# draft5_4lyr_autoroute.net
KiCad netlist of a schematic drawn in EAGLE
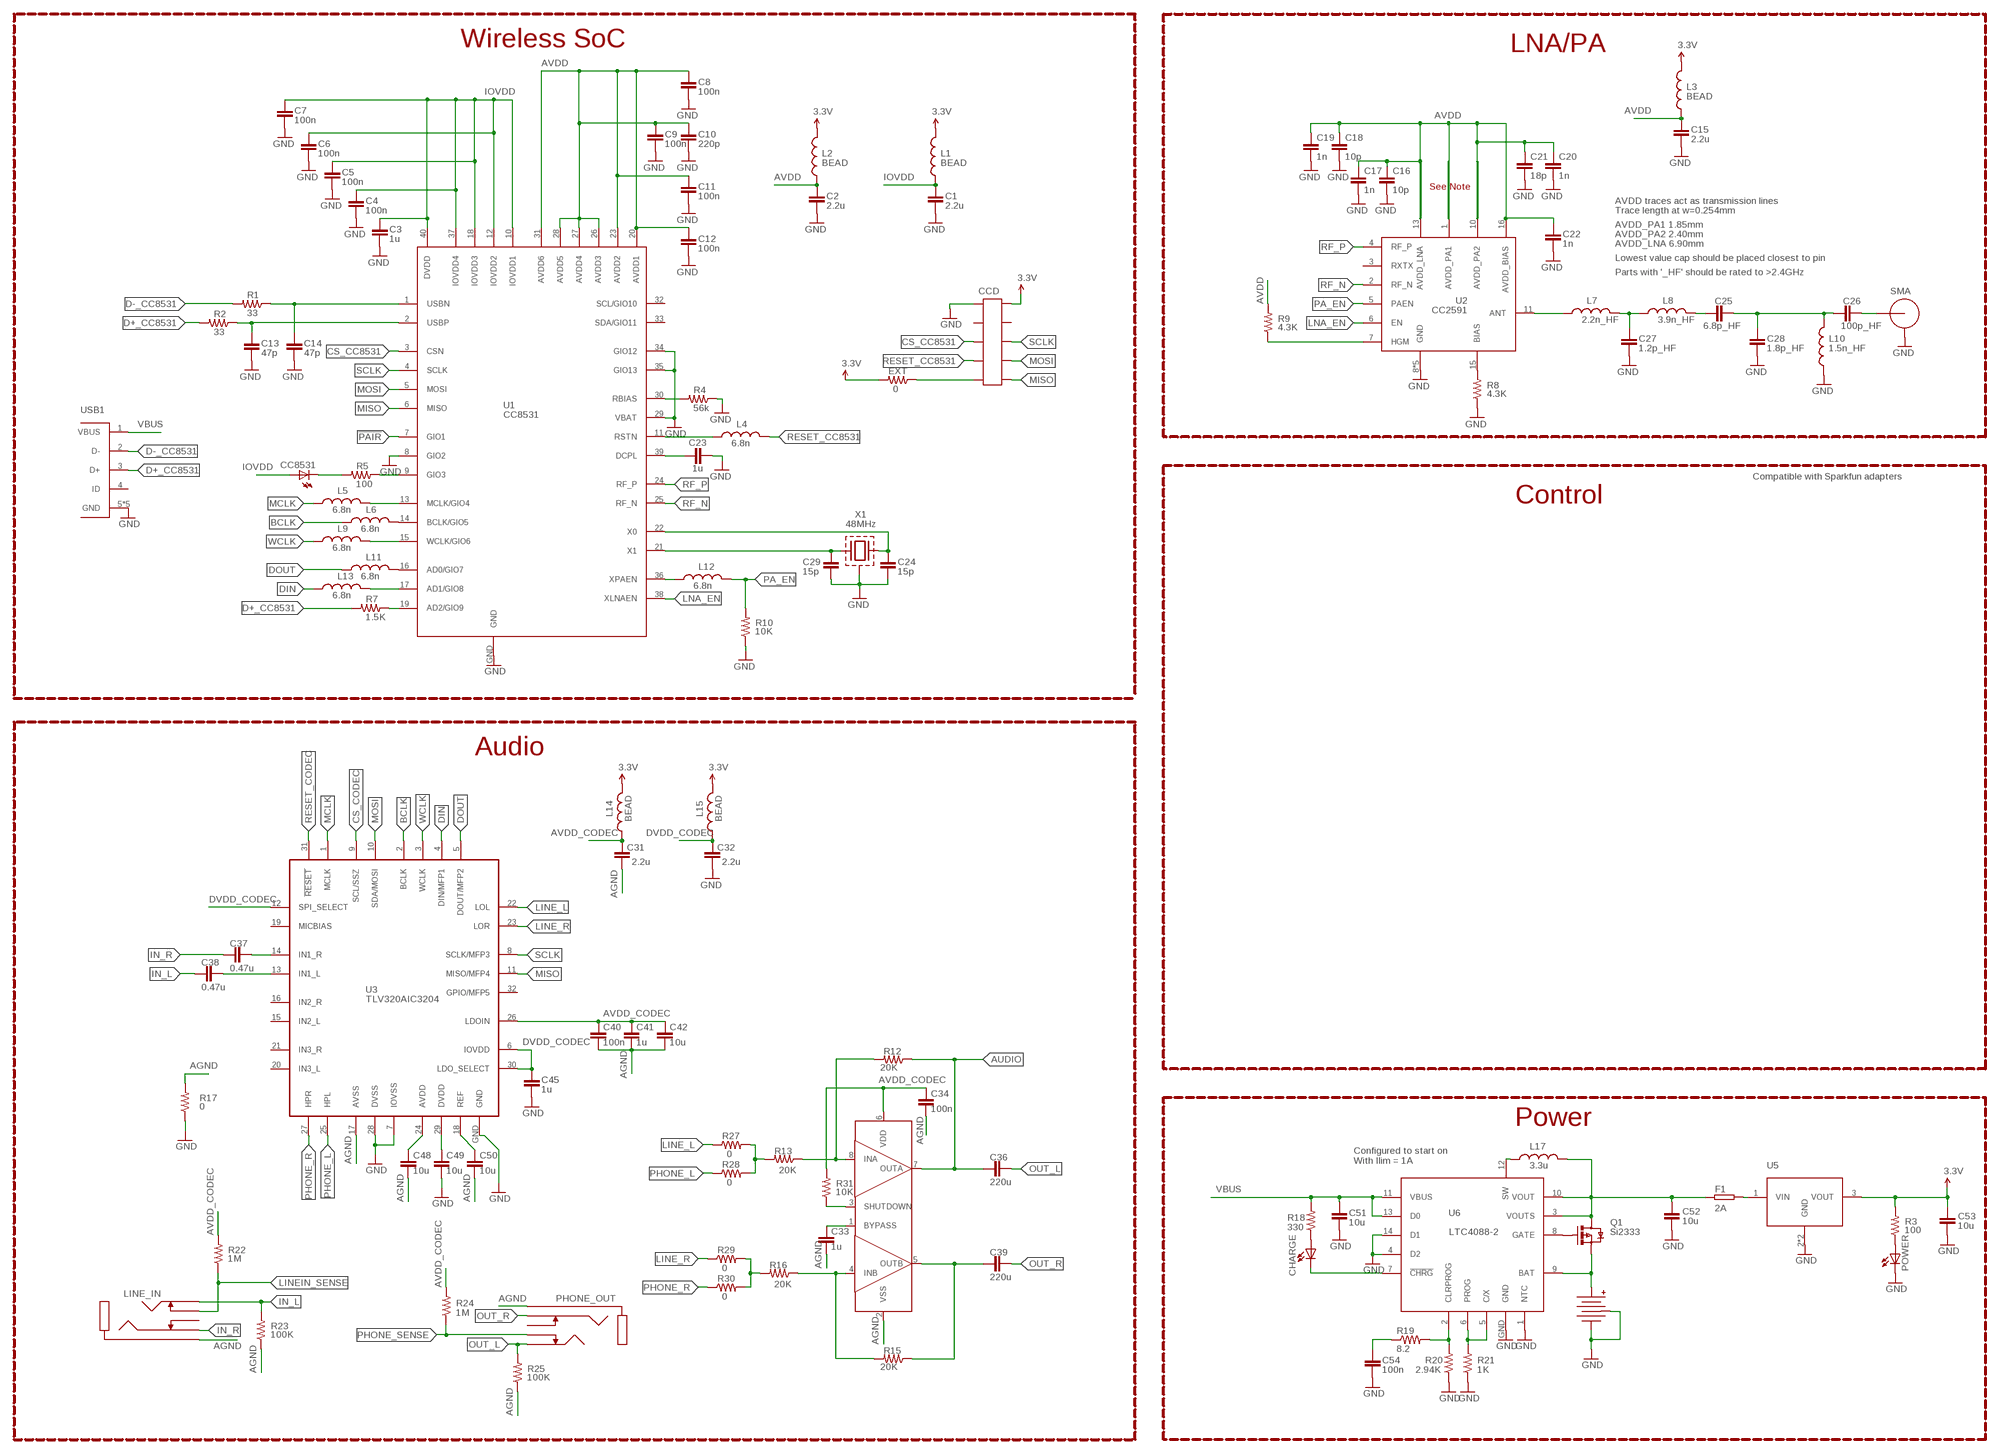
[diagram p0: schematic, sheet 1, part 1 of 2]
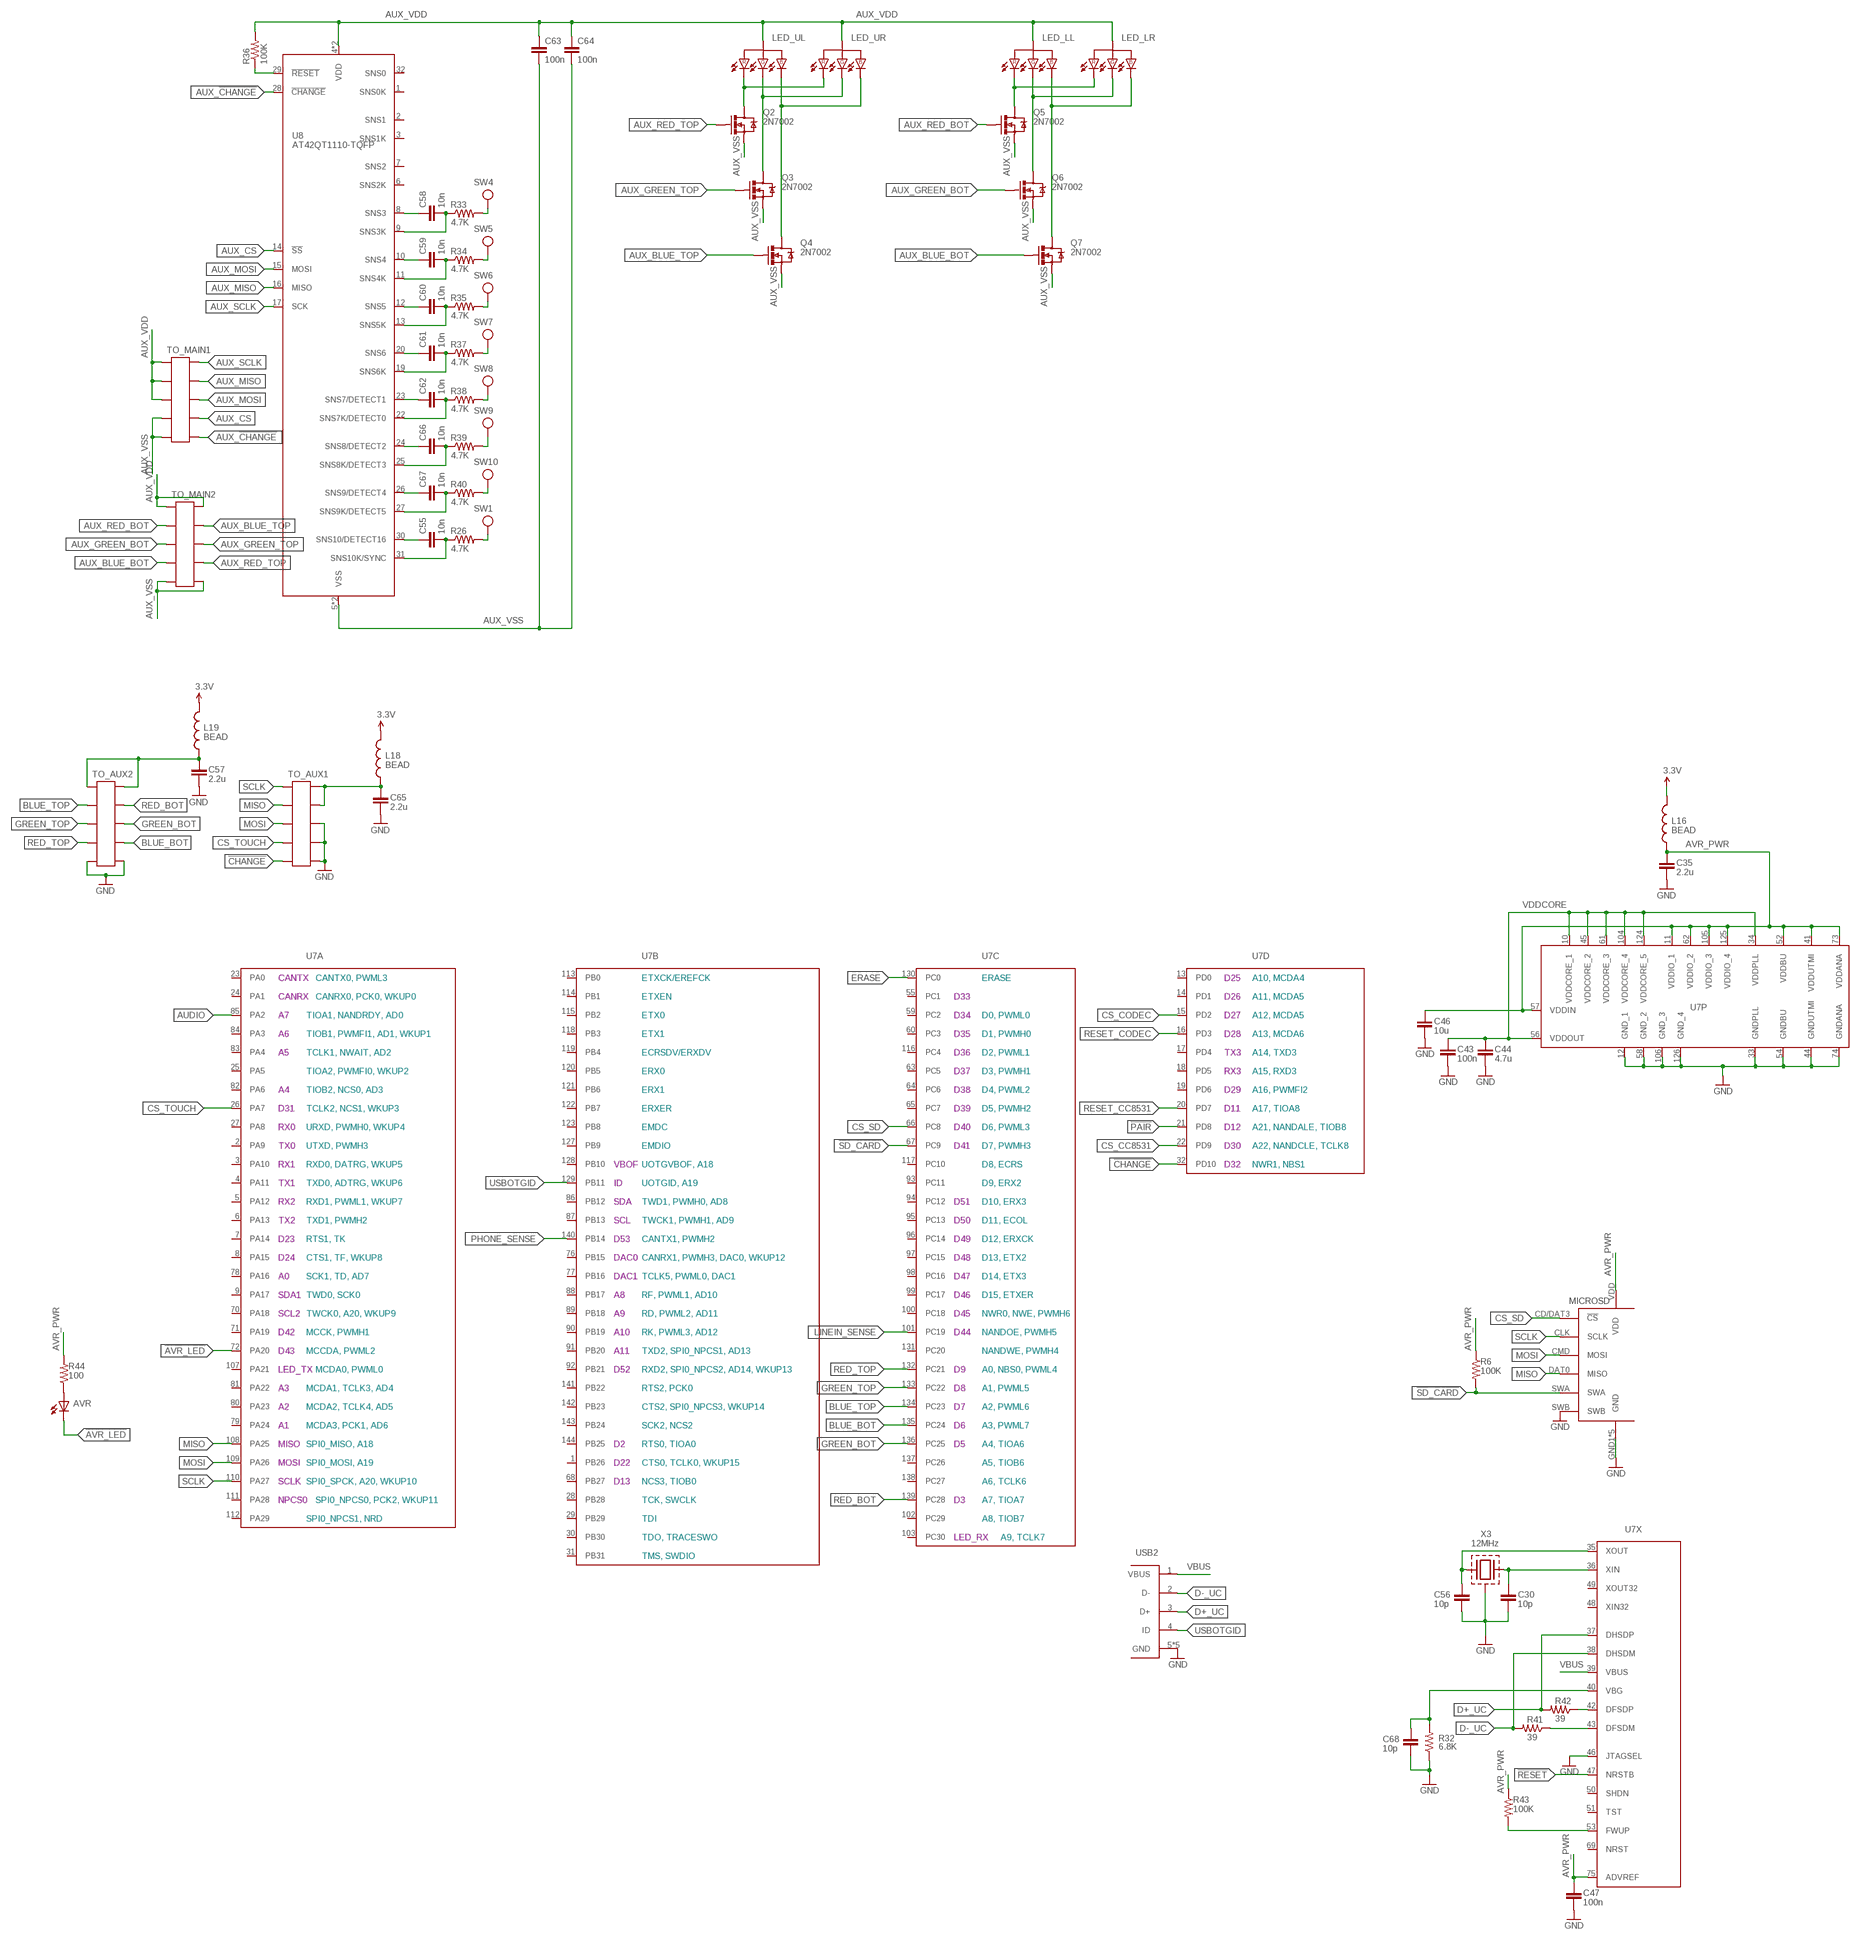
[diagram p1: schematic, sheet 1, part 2 of 2]

(export (version "E")
  (design (tool "Eeschema 10.0.6"))
  (components
    (comp (ref "AVR")
      (value "LED1206")
      (footprint "eagle-import:LED-1206")
      (libsource (lib "eagle-import") (part "LED1206"))
    )
    (comp (ref "BATTERY")
      (value "BATTERY-LIPO-JST")
      (footprint "eagle-import:1775469-2")
      (libsource (lib "eagle-import") (part "BATTERY-LIPO-JST"))
    )
    (comp (ref "C1")
      (value "2.2u")
      (footprint "eagle-import:C0603")
      (libsource (lib "eagle-import") (part "rcl_C-EUC0603"))
    )
    (comp (ref "C2")
      (value "2.2u")
      (footprint "eagle-import:C0603")
      (libsource (lib "eagle-import") (part "rcl_C-EUC0603"))
    )
    (comp (ref "C3")
      (value "1u")
      (footprint "eagle-import:C0603")
      (libsource (lib "eagle-import") (part "rcl_C-EUC0603"))
    )
    (comp (ref "C4")
      (value "100n")
      (footprint "eagle-import:C0603")
      (libsource (lib "eagle-import") (part "rcl_C-EUC0603"))
    )
    (comp (ref "C5")
      (value "100n")
      (footprint "eagle-import:C0603")
      (libsource (lib "eagle-import") (part "rcl_C-EUC0603"))
    )
    (comp (ref "C6")
      (value "100n")
      (footprint "eagle-import:C0603")
      (libsource (lib "eagle-import") (part "rcl_C-EUC0603"))
    )
    (comp (ref "C7")
      (value "100n")
      (footprint "eagle-import:C0603")
      (libsource (lib "eagle-import") (part "rcl_C-EUC0603"))
    )
    (comp (ref "C8")
      (value "100n")
      (footprint "eagle-import:C0603")
      (libsource (lib "eagle-import") (part "rcl_C-EUC0603"))
    )
    (comp (ref "C9")
      (value "100n")
      (footprint "eagle-import:C0603")
      (libsource (lib "eagle-import") (part "rcl_C-EUC0603"))
    )
    (comp (ref "C10")
      (value "220p")
      (footprint "eagle-import:C0603")
      (libsource (lib "eagle-import") (part "rcl_C-EUC0603"))
    )
    (comp (ref "C11")
      (value "100n")
      (footprint "eagle-import:C0603")
      (libsource (lib "eagle-import") (part "rcl_C-EUC0603"))
    )
    (comp (ref "C12")
      (value "100n")
      (footprint "eagle-import:C0603")
      (libsource (lib "eagle-import") (part "rcl_C-EUC0603"))
    )
    (comp (ref "C13")
      (value "47p")
      (footprint "eagle-import:C0603")
      (libsource (lib "eagle-import") (part "rcl_C-EUC0603"))
    )
    (comp (ref "C14")
      (value "47p")
      (footprint "eagle-import:C0603")
      (libsource (lib "eagle-import") (part "rcl_C-EUC0603"))
    )
    (comp (ref "C15")
      (value "2.2u")
      (footprint "eagle-import:C0603")
      (libsource (lib "eagle-import") (part "rcl_C-EUC0603"))
    )
    (comp (ref "C16")
      (value "10p")
      (footprint "eagle-import:C0603")
      (libsource (lib "eagle-import") (part "rcl_C-EUC0603"))
    )
    (comp (ref "C17")
      (value "1n")
      (footprint "eagle-import:C0603")
      (libsource (lib "eagle-import") (part "rcl_C-EUC0603"))
    )
    (comp (ref "C18")
      (value "10p")
      (footprint "eagle-import:C0603")
      (libsource (lib "eagle-import") (part "rcl_C-EUC0603"))
    )
    (comp (ref "C19")
      (value "1n")
      (footprint "eagle-import:C0603")
      (libsource (lib "eagle-import") (part "rcl_C-EUC0603"))
    )
    (comp (ref "C20")
      (value "1n")
      (footprint "eagle-import:C0603")
      (libsource (lib "eagle-import") (part "rcl_C-EUC0603"))
    )
    (comp (ref "C21")
      (value "18p")
      (footprint "eagle-import:C0603")
      (libsource (lib "eagle-import") (part "rcl_C-EUC0603"))
    )
    (comp (ref "C22")
      (value "1n")
      (footprint "eagle-import:C0603")
      (libsource (lib "eagle-import") (part "rcl_C-EUC0603"))
    )
    (comp (ref "C23")
      (value "1u")
      (footprint "eagle-import:C0603")
      (libsource (lib "eagle-import") (part "rcl_C-EUC0603"))
    )
    (comp (ref "C24")
      (value "15p")
      (footprint "eagle-import:C0603")
      (libsource (lib "eagle-import") (part "rcl_C-EUC0603"))
    )
    (comp (ref "C25")
      (value "6.8p_HF")
      (footprint "eagle-import:C0603")
      (libsource (lib "eagle-import") (part "rcl_C-EUC0603"))
    )
    (comp (ref "C26")
      (value "100p_HF")
      (footprint "eagle-import:C0603")
      (libsource (lib "eagle-import") (part "rcl_C-EUC0603"))
    )
    (comp (ref "C27")
      (value "1.2p_HF")
      (footprint "eagle-import:C0603")
      (libsource (lib "eagle-import") (part "rcl_C-EUC0603"))
    )
    (comp (ref "C28")
      (value "1.8p_HF")
      (footprint "eagle-import:C0603")
      (libsource (lib "eagle-import") (part "rcl_C-EUC0603"))
    )
    (comp (ref "C29")
      (value "15p")
      (footprint "eagle-import:C0603")
      (libsource (lib "eagle-import") (part "rcl_C-EUC0603"))
    )
    (comp (ref "C30")
      (value "10p")
      (footprint "eagle-import:C0603")
      (libsource (lib "eagle-import") (part "C-EUC0603"))
    )
    (comp (ref "C31")
      (value "2.2u")
      (footprint "eagle-import:C0603")
      (libsource (lib "eagle-import") (part "rcl_C-EUC0603"))
    )
    (comp (ref "C32")
      (value "2.2u")
      (footprint "eagle-import:C0603")
      (libsource (lib "eagle-import") (part "rcl_C-EUC0603"))
    )
    (comp (ref "C33")
      (value "1u")
      (footprint "eagle-import:C0603")
      (libsource (lib "eagle-import") (part "rcl_C-EUC0603"))
    )
    (comp (ref "C34")
      (value "100n")
      (footprint "eagle-import:C0603")
      (libsource (lib "eagle-import") (part "rcl_C-EUC0603"))
    )
    (comp (ref "C35")
      (value "2.2u")
      (footprint "eagle-import:C0603")
      (libsource (lib "eagle-import") (part "rcl_C-EUC0603"))
    )
    (comp (ref "C36")
      (value "220u")
      (footprint "eagle-import:C1210")
      (libsource (lib "eagle-import") (part "C-EUC1210"))
    )
    (comp (ref "C37")
      (value "0.47u")
      (footprint "eagle-import:C0603")
      (libsource (lib "eagle-import") (part "rcl_C-EUC0603"))
    )
    (comp (ref "C38")
      (value "0.47u")
      (footprint "eagle-import:C0603")
      (libsource (lib "eagle-import") (part "rcl_C-EUC0603"))
    )
    (comp (ref "C39")
      (value "220u")
      (footprint "eagle-import:C1210")
      (libsource (lib "eagle-import") (part "C-EUC1210"))
    )
    (comp (ref "C40")
      (value "100n")
      (footprint "eagle-import:C0603")
      (libsource (lib "eagle-import") (part "rcl_C-EUC0603"))
    )
    (comp (ref "C41")
      (value "1u")
      (footprint "eagle-import:C0603")
      (libsource (lib "eagle-import") (part "rcl_C-EUC0603"))
    )
    (comp (ref "C42")
      (value "10u")
      (footprint "eagle-import:C0603")
      (libsource (lib "eagle-import") (part "rcl_C-EUC0603"))
    )
    (comp (ref "C43")
      (value "100n")
      (footprint "eagle-import:C0603")
      (libsource (lib "eagle-import") (part "rcl_C-EUC0603"))
    )
    (comp (ref "C44")
      (value "4.7u")
      (footprint "eagle-import:C0603")
      (libsource (lib "eagle-import") (part "rcl_C-EUC0603"))
    )
    (comp (ref "C45")
      (value "1u")
      (footprint "eagle-import:C0603")
      (libsource (lib "eagle-import") (part "rcl_C-EUC0603"))
    )
    (comp (ref "C46")
      (value "10u")
      (footprint "eagle-import:C0603")
      (libsource (lib "eagle-import") (part "rcl_C-EUC0603"))
    )
    (comp (ref "C47")
      (value "100n")
      (footprint "eagle-import:C0603")
      (libsource (lib "eagle-import") (part "rcl_C-EUC0603"))
    )
    (comp (ref "C48")
      (value "10u")
      (footprint "eagle-import:C0603")
      (libsource (lib "eagle-import") (part "rcl_C-EUC0603"))
    )
    (comp (ref "C49")
      (value "10u")
      (footprint "eagle-import:C0603")
      (libsource (lib "eagle-import") (part "rcl_C-EUC0603"))
    )
    (comp (ref "C50")
      (value "10u")
      (footprint "eagle-import:C0603")
      (libsource (lib "eagle-import") (part "rcl_C-EUC0603"))
    )
    (comp (ref "C51")
      (value "10u")
      (footprint "eagle-import:C0603")
      (libsource (lib "eagle-import") (part "C-EUC0603"))
    )
    (comp (ref "C52")
      (value "10u")
      (footprint "eagle-import:C0603")
      (libsource (lib "eagle-import") (part "rcl_C-EUC0603"))
    )
    (comp (ref "C53")
      (value "10u")
      (footprint "eagle-import:C0603")
      (libsource (lib "eagle-import") (part "rcl_C-EUC0603"))
    )
    (comp (ref "C54")
      (value "100n")
      (footprint "eagle-import:C0603")
      (libsource (lib "eagle-import") (part "C-EUC0603"))
    )
    (comp (ref "C55")
      (value "10n")
      (footprint "eagle-import:C0603")
      (libsource (lib "eagle-import") (part "rcl_C-EUC0603"))
    )
    (comp (ref "C56")
      (value "10p")
      (footprint "eagle-import:C0603")
      (libsource (lib "eagle-import") (part "C-EUC0603"))
    )
    (comp (ref "C57")
      (value "2.2u")
      (footprint "eagle-import:C0603")
      (libsource (lib "eagle-import") (part "rcl_C-EUC0603"))
    )
    (comp (ref "C58")
      (value "10n")
      (footprint "eagle-import:C0603")
      (libsource (lib "eagle-import") (part "rcl_C-EUC0603"))
    )
    (comp (ref "C59")
      (value "10n")
      (footprint "eagle-import:C0603")
      (libsource (lib "eagle-import") (part "rcl_C-EUC0603"))
    )
    (comp (ref "C60")
      (value "10n")
      (footprint "eagle-import:C0603")
      (libsource (lib "eagle-import") (part "rcl_C-EUC0603"))
    )
    (comp (ref "C61")
      (value "10n")
      (footprint "eagle-import:C0603")
      (libsource (lib "eagle-import") (part "rcl_C-EUC0603"))
    )
    (comp (ref "C62")
      (value "10n")
      (footprint "eagle-import:C0603")
      (libsource (lib "eagle-import") (part "rcl_C-EUC0603"))
    )
    (comp (ref "C63")
      (value "100n")
      (footprint "eagle-import:C0603")
      (libsource (lib "eagle-import") (part "rcl_C-EUC0603"))
    )
    (comp (ref "C64")
      (value "100n")
      (footprint "eagle-import:C0603")
      (libsource (lib "eagle-import") (part "rcl_C-EUC0603"))
    )
    (comp (ref "C65")
      (value "2.2u")
      (footprint "eagle-import:C0603")
      (libsource (lib "eagle-import") (part "rcl_C-EUC0603"))
    )
    (comp (ref "C66")
      (value "10n")
      (footprint "eagle-import:C0603")
      (libsource (lib "eagle-import") (part "rcl_C-EUC0603"))
    )
    (comp (ref "C67")
      (value "10n")
      (footprint "eagle-import:C0603")
      (libsource (lib "eagle-import") (part "rcl_C-EUC0603"))
    )
    (comp (ref "C68")
      (value "10p")
      (footprint "eagle-import:C0603")
      (libsource (lib "eagle-import") (part "C-EUC0603"))
    )
    (comp (ref "CC8531")
      (value "LED1206")
      (footprint "eagle-import:LED-1206")
      (libsource (lib "eagle-import") (part "LED1206"))
    )
    (comp (ref "CCD")
      (value "HEADER-10P-SMD-MALE2")
      (footprint "eagle-import:HEADER-10P-1.27MM")
      (libsource (lib "eagle-import") (part "HEADER-10P-SMD-MALE2"))
    )
    (comp (ref "CHARGE")
      (value "LED1206")
      (footprint "eagle-import:LED-1206")
      (libsource (lib "eagle-import") (part "LED1206"))
    )
    (comp (ref "EXT")
      (value "0")
      (footprint "eagle-import:R0603")
      (libsource (lib "eagle-import") (part "rcl_R-US_R0603"))
    )
    (comp (ref "F1")
      (value "2A")
      (footprint "eagle-import:1210")
      (libsource (lib "eagle-import") (part "PTC_FUSE"))
    )
    (comp (ref "L1")
      (value "BEAD")
      (footprint "eagle-import:0603")
      (libsource (lib "eagle-import") (part "INDUCTOR0603"))
    )
    (comp (ref "L2")
      (value "BEAD")
      (footprint "eagle-import:0603")
      (libsource (lib "eagle-import") (part "INDUCTOR0603"))
    )
    (comp (ref "L3")
      (value "BEAD")
      (footprint "eagle-import:0603")
      (libsource (lib "eagle-import") (part "INDUCTOR0603"))
    )
    (comp (ref "L4")
      (value "6.8n")
      (footprint "eagle-import:0603")
      (libsource (lib "eagle-import") (part "INDUCTOR0603"))
    )
    (comp (ref "L5")
      (value "6.8n")
      (footprint "eagle-import:0603")
      (libsource (lib "eagle-import") (part "INDUCTOR0603"))
    )
    (comp (ref "L6")
      (value "6.8n")
      (footprint "eagle-import:0603")
      (libsource (lib "eagle-import") (part "INDUCTOR0603"))
    )
    (comp (ref "L7")
      (value "2.2n_HF")
      (footprint "eagle-import:0603")
      (libsource (lib "eagle-import") (part "INDUCTOR0603"))
    )
    (comp (ref "L8")
      (value "3.9n_HF")
      (footprint "eagle-import:0603")
      (libsource (lib "eagle-import") (part "INDUCTOR0603"))
    )
    (comp (ref "L9")
      (value "6.8n")
      (footprint "eagle-import:0603")
      (libsource (lib "eagle-import") (part "INDUCTOR0603"))
    )
    (comp (ref "L10")
      (value "1.5n_HF")
      (footprint "eagle-import:0603")
      (libsource (lib "eagle-import") (part "INDUCTOR0603"))
    )
    (comp (ref "L11")
      (value "6.8n")
      (footprint "eagle-import:0603")
      (libsource (lib "eagle-import") (part "INDUCTOR0603"))
    )
    (comp (ref "L12")
      (value "6.8n")
      (footprint "eagle-import:0603")
      (libsource (lib "eagle-import") (part "INDUCTOR0603"))
    )
    (comp (ref "L13")
      (value "6.8n")
      (footprint "eagle-import:0603")
      (libsource (lib "eagle-import") (part "INDUCTOR0603"))
    )
    (comp (ref "L14")
      (value "BEAD")
      (footprint "eagle-import:0603")
      (libsource (lib "eagle-import") (part "INDUCTOR0603"))
    )
    (comp (ref "L15")
      (value "BEAD")
      (footprint "eagle-import:0603")
      (libsource (lib "eagle-import") (part "INDUCTOR0603"))
    )
    (comp (ref "L16")
      (value "BEAD")
      (footprint "eagle-import:0603")
      (libsource (lib "eagle-import") (part "INDUCTOR0603"))
    )
    (comp (ref "L17")
      (value "3.3u")
      (footprint "eagle-import:IFSC-1111AB-01")
      (libsource (lib "eagle-import") (part "IFSC-1111AB-01"))
    )
    (comp (ref "L18")
      (value "BEAD")
      (footprint "eagle-import:0603")
      (libsource (lib "eagle-import") (part "INDUCTOR0603"))
    )
    (comp (ref "L19")
      (value "BEAD")
      (footprint "eagle-import:0603")
      (libsource (lib "eagle-import") (part "INDUCTOR0603"))
    )
    (comp (ref "LED_LL")
      (value "LED_RGB")
      (footprint "eagle-import:PLCC-4")
      (libsource (lib "eagle-import") (part "LED_RGB"))
    )
    (comp (ref "LED_LR")
      (value "LED_RGB")
      (footprint "eagle-import:PLCC-4")
      (libsource (lib "eagle-import") (part "LED_RGB"))
    )
    (comp (ref "LED_UL")
      (value "LED_RGB")
      (footprint "eagle-import:PLCC-4")
      (libsource (lib "eagle-import") (part "LED_RGB"))
    )
    (comp (ref "LED_UR")
      (value "LED_RGB")
      (footprint "eagle-import:PLCC-4")
      (libsource (lib "eagle-import") (part "LED_RGB"))
    )
    (comp (ref "LINE_IN")
      (value "PHONE_SW-STX-35332-5N")
      (footprint "eagle-import:STX-35332-5N")
      (libsource (lib "eagle-import") (part "PHONE_SW-STX-35332-5N"))
    )
    (comp (ref "MICROSD")
      (value "MICROSD104031-0811")
      (footprint "eagle-import:MOLEX_104031-0811")
      (libsource (lib "eagle-import") (part "MICROSD104031-0811"))
    )
    (comp (ref "PHONE_OUT")
      (value "PHONE_SW-STX-35332-5N")
      (footprint "eagle-import:STX-35332-5N")
      (libsource (lib "eagle-import") (part "PHONE_SW-STX-35332-5N"))
    )
    (comp (ref "POWER")
      (value "LED1206")
      (footprint "eagle-import:LED-1206")
      (libsource (lib "eagle-import") (part "LED1206"))
    )
    (comp (ref "Q1")
      (value "Si2333")
      (footprint "eagle-import:SOT23-3")
      (libsource (lib "eagle-import") (part "MOSFET-PCHANNELSMD"))
    )
    (comp (ref "Q2")
      (value "2N7002")
      (footprint "eagle-import:SOT23-3")
      (libsource (lib "eagle-import") (part "MOSFET-NCHANNELSMD"))
    )
    (comp (ref "Q3")
      (value "2N7002")
      (footprint "eagle-import:SOT23-3")
      (libsource (lib "eagle-import") (part "MOSFET-NCHANNELSMD"))
    )
    (comp (ref "Q4")
      (value "2N7002")
      (footprint "eagle-import:SOT23-3")
      (libsource (lib "eagle-import") (part "MOSFET-NCHANNELSMD"))
    )
    (comp (ref "Q5")
      (value "2N7002")
      (footprint "eagle-import:SOT23-3")
      (libsource (lib "eagle-import") (part "MOSFET-NCHANNELSMD"))
    )
    (comp (ref "Q6")
      (value "2N7002")
      (footprint "eagle-import:SOT23-3")
      (libsource (lib "eagle-import") (part "MOSFET-NCHANNELSMD"))
    )
    (comp (ref "Q7")
      (value "2N7002")
      (footprint "eagle-import:SOT23-3")
      (libsource (lib "eagle-import") (part "MOSFET-NCHANNELSMD"))
    )
    (comp (ref "R1")
      (value "33")
      (footprint "eagle-import:R0603")
      (libsource (lib "eagle-import") (part "rcl_R-US_R0603"))
    )
    (comp (ref "R2")
      (value "33")
      (footprint "eagle-import:R0603")
      (libsource (lib "eagle-import") (part "rcl_R-US_R0603"))
    )
    (comp (ref "R3")
      (value "100")
      (footprint "eagle-import:R0603")
      (libsource (lib "eagle-import") (part "rcl_R-US_R0603"))
    )
    (comp (ref "R4")
      (value "56k")
      (footprint "eagle-import:R0603")
      (libsource (lib "eagle-import") (part "rcl_R-US_R0603"))
    )
    (comp (ref "R5")
      (value "100")
      (footprint "eagle-import:R0603")
      (libsource (lib "eagle-import") (part "rcl_R-US_R0603"))
    )
    (comp (ref "R6")
      (value "100K")
      (footprint "eagle-import:R0603")
      (libsource (lib "eagle-import") (part "rcl_R-US_R0603"))
    )
    (comp (ref "R7")
      (value "1.5K")
      (footprint "eagle-import:R0603")
      (libsource (lib "eagle-import") (part "rcl_R-US_R0603"))
    )
    (comp (ref "R8")
      (value "4.3K")
      (footprint "eagle-import:R0603")
      (libsource (lib "eagle-import") (part "rcl_R-US_R0603"))
    )
    (comp (ref "R9")
      (value "4.3K")
      (footprint "eagle-import:R0603")
      (libsource (lib "eagle-import") (part "rcl_R-US_R0603"))
    )
    (comp (ref "R10")
      (value "10K")
      (footprint "eagle-import:R0603")
      (libsource (lib "eagle-import") (part "rcl_R-US_R0603"))
    )
    (comp (ref "R12")
      (value "20K")
      (footprint "eagle-import:R0603")
      (libsource (lib "eagle-import") (part "R-US_R0603"))
    )
    (comp (ref "R13")
      (value "20K")
      (footprint "eagle-import:R0603")
      (libsource (lib "eagle-import") (part "R-US_R0603"))
    )
    (comp (ref "R15")
      (value "20K")
      (footprint "eagle-import:R0603")
      (libsource (lib "eagle-import") (part "R-US_R0603"))
    )
    (comp (ref "R16")
      (value "20K")
      (footprint "eagle-import:R0603")
      (libsource (lib "eagle-import") (part "R-US_R0603"))
    )
    (comp (ref "R17")
      (value "0")
      (footprint "eagle-import:R0603")
      (libsource (lib "eagle-import") (part "rcl_R-US_R0603"))
    )
    (comp (ref "R18")
      (value "330")
      (footprint "eagle-import:R0603")
      (libsource (lib "eagle-import") (part "R-US_R0603"))
    )
    (comp (ref "R19")
      (value "8.2")
      (footprint "eagle-import:R0603")
      (libsource (lib "eagle-import") (part "R-US_R0603"))
    )
    (comp (ref "R20")
      (value "2.94K")
      (footprint "eagle-import:R0603")
      (libsource (lib "eagle-import") (part "R-US_R0603"))
    )
    (comp (ref "R21")
      (value "1K")
      (footprint "eagle-import:R0603")
      (libsource (lib "eagle-import") (part "R-US_R0603"))
    )
    (comp (ref "R22")
      (value "1M")
      (footprint "eagle-import:R0603")
      (libsource (lib "eagle-import") (part "rcl_R-US_R0603"))
    )
    (comp (ref "R23")
      (value "100K")
      (footprint "eagle-import:R0603")
      (libsource (lib "eagle-import") (part "rcl_R-US_R0603"))
    )
    (comp (ref "R24")
      (value "1M")
      (footprint "eagle-import:R0603")
      (libsource (lib "eagle-import") (part "rcl_R-US_R0603"))
    )
    (comp (ref "R25")
      (value "100K")
      (footprint "eagle-import:R0603")
      (libsource (lib "eagle-import") (part "rcl_R-US_R0603"))
    )
    (comp (ref "R26")
      (value "4.7K")
      (footprint "eagle-import:R0603")
      (libsource (lib "eagle-import") (part "rcl_R-US_R0603"))
    )
    (comp (ref "R27")
      (value "0")
      (footprint "eagle-import:R0603")
      (libsource (lib "eagle-import") (part "R-US_R0603"))
    )
    (comp (ref "R28")
      (value "0")
      (footprint "eagle-import:R0603")
      (libsource (lib "eagle-import") (part "R-US_R0603"))
    )
    (comp (ref "R29")
      (value "0")
      (footprint "eagle-import:R0603")
      (libsource (lib "eagle-import") (part "R-US_R0603"))
    )
    (comp (ref "R30")
      (value "0")
      (footprint "eagle-import:R0603")
      (libsource (lib "eagle-import") (part "R-US_R0603"))
    )
    (comp (ref "R31")
      (value "10K")
      (footprint "eagle-import:R0603")
      (libsource (lib "eagle-import") (part "rcl_R-US_R0603"))
    )
    (comp (ref "R32")
      (value "6.8K")
      (footprint "eagle-import:R0603")
      (libsource (lib "eagle-import") (part "rcl_R-US_R0603"))
    )
    (comp (ref "R33")
      (value "4.7K")
      (footprint "eagle-import:R0603")
      (libsource (lib "eagle-import") (part "rcl_R-US_R0603"))
    )
    (comp (ref "R34")
      (value "4.7K")
      (footprint "eagle-import:R0603")
      (libsource (lib "eagle-import") (part "rcl_R-US_R0603"))
    )
    (comp (ref "R35")
      (value "4.7K")
      (footprint "eagle-import:R0603")
      (libsource (lib "eagle-import") (part "rcl_R-US_R0603"))
    )
    (comp (ref "R36")
      (value "100K")
      (footprint "eagle-import:R0603")
      (libsource (lib "eagle-import") (part "rcl_R-US_R0603"))
    )
    (comp (ref "R37")
      (value "4.7K")
      (footprint "eagle-import:R0603")
      (libsource (lib "eagle-import") (part "rcl_R-US_R0603"))
    )
    (comp (ref "R38")
      (value "4.7K")
      (footprint "eagle-import:R0603")
      (libsource (lib "eagle-import") (part "rcl_R-US_R0603"))
    )
    (comp (ref "R39")
      (value "4.7K")
      (footprint "eagle-import:R0603")
      (libsource (lib "eagle-import") (part "rcl_R-US_R0603"))
    )
    (comp (ref "R40")
      (value "4.7K")
      (footprint "eagle-import:R0603")
      (libsource (lib "eagle-import") (part "rcl_R-US_R0603"))
    )
    (comp (ref "R41")
      (value "39")
      (footprint "eagle-import:R0603")
      (libsource (lib "eagle-import") (part "rcl_R-US_R0603"))
    )
    (comp (ref "R42")
      (value "39")
      (footprint "eagle-import:R0603")
      (libsource (lib "eagle-import") (part "rcl_R-US_R0603"))
    )
    (comp (ref "R43")
      (value "100K")
      (footprint "eagle-import:R0603")
      (libsource (lib "eagle-import") (part "rcl_R-US_R0603"))
    )
    (comp (ref "R44")
      (value "100")
      (footprint "eagle-import:R0603")
      (libsource (lib "eagle-import") (part "rcl_R-US_R0603"))
    )
    (comp (ref "SMA")
      (value "SMA-REVSMA-0.62")
      (footprint "eagle-import:CONREVSMA003.062")
      (libsource (lib "eagle-import") (part "SMA-REVSMA-0.62"))
    )
    (comp (ref "SW1")
      (value "TOUCH_PAD-CIRCLE-15MM")
      (footprint "eagle-import:TOUCH-CIRCLE-15MM")
      (libsource (lib "eagle-import") (part "TOUCH_PAD-CIRCLE-15MM"))
    )
    (comp (ref "SW4")
      (value "TOUCH_PAD-CIRCLE-15MM")
      (footprint "eagle-import:TOUCH-CIRCLE-15MM")
      (libsource (lib "eagle-import") (part "TOUCH_PAD-CIRCLE-15MM"))
    )
    (comp (ref "SW5")
      (value "TOUCH_PAD-CIRCLE-15MM")
      (footprint "eagle-import:TOUCH-CIRCLE-15MM")
      (libsource (lib "eagle-import") (part "TOUCH_PAD-CIRCLE-15MM"))
    )
    (comp (ref "SW6")
      (value "TOUCH_PAD-CIRCLE-15MM")
      (footprint "eagle-import:TOUCH-CIRCLE-15MM")
      (libsource (lib "eagle-import") (part "TOUCH_PAD-CIRCLE-15MM"))
    )
    (comp (ref "SW7")
      (value "TOUCH_PAD-CIRCLE-15MM")
      (footprint "eagle-import:TOUCH-CIRCLE-15MM")
      (libsource (lib "eagle-import") (part "TOUCH_PAD-CIRCLE-15MM"))
    )
    (comp (ref "SW8")
      (value "TOUCH_PAD-CIRCLE-15MM")
      (footprint "eagle-import:TOUCH-CIRCLE-15MM")
      (libsource (lib "eagle-import") (part "TOUCH_PAD-CIRCLE-15MM"))
    )
    (comp (ref "SW9")
      (value "TOUCH_PAD-CIRCLE-15MM")
      (footprint "eagle-import:TOUCH-CIRCLE-15MM")
      (libsource (lib "eagle-import") (part "TOUCH_PAD-CIRCLE-15MM"))
    )
    (comp (ref "SW10")
      (value "TOUCH_PAD-CIRCLE-15MM")
      (footprint "eagle-import:TOUCH-CIRCLE-15MM")
      (libsource (lib "eagle-import") (part "TOUCH_PAD-CIRCLE-15MM"))
    )
    (comp (ref "TO_AUX1")
      (value "HEADER-10P-SMD-2MM-FEMALE")
      (footprint "eagle-import:M22-63405")
      (libsource (lib "eagle-import") (part "HEADER-10P-SMD-2MM-FEMALE"))
    )
    (comp (ref "TO_AUX2")
      (value "HEADER-10P-SMD-2MM-FEMALE")
      (footprint "eagle-import:M22-63405")
      (libsource (lib "eagle-import") (part "HEADER-10P-SMD-2MM-FEMALE"))
    )
    (comp (ref "TO_MAIN1")
      (value "HEADER-10P-SMD-2MM-MALE")
      (footprint "eagle-import:M22-53205")
      (libsource (lib "eagle-import") (part "HEADER-10P-SMD-2MM-MALE"))
    )
    (comp (ref "TO_MAIN2")
      (value "HEADER-10P-SMD-2MM-MALE")
      (footprint "eagle-import:M22-53205")
      (libsource (lib "eagle-import") (part "HEADER-10P-SMD-2MM-MALE"))
    )
    (comp (ref "U1")
      (value "CC8531")
      (footprint "eagle-import:S-PVQFN-N40")
      (libsource (lib "eagle-import") (part "CC8531"))
    )
    (comp (ref "U2")
      (value "CC2591")
      (footprint "eagle-import:S-PVQFN-N16")
      (libsource (lib "eagle-import") (part "CC2591"))
    )
    (comp (ref "U3")
      (value "TLV320AIC3204")
      (footprint "eagle-import:S-PVQFN-N32")
      (libsource (lib "eagle-import") (part "TLV320AIC3204"))
    )
    (comp (ref "U5")
      (value "MCP1826-SOT223")
      (footprint "eagle-import:SOT-223")
      (libsource (lib "eagle-import") (part "MCP1826-SOT223"))
    )
    (comp (ref "U6")
      (value "LTC4088-2")
      (footprint "eagle-import:DFN-14")
      (libsource (lib "eagle-import") (part "LTC4088-1/2"))
    )
    (comp (ref "U7")
      (value "ATSAM3X8E_ALT-LQFP-144")
      (footprint "eagle-import:LQFP-144")
      (libsource (lib "eagle-import") (part "ATSAM3X8E_ALT-LQFP-144"))
    )
    (comp (ref "U8")
      (value "AT42QT1110-TQFP")
      (footprint "eagle-import:S-PQFP-N32")
      (libsource (lib "eagle-import") (part "AT42QT1110-TQFP"))
    )
    (comp (ref "U9")
      (value "LM4881")
      (footprint "eagle-import:SO08")
      (libsource (lib "eagle-import") (part "LM4881"))
    )
    (comp (ref "USB1")
      (value "USB_MICRO_AB")
      (footprint "eagle-import:USB_MICRO_AB")
      (libsource (lib "eagle-import") (part "USB_MICRO_AB"))
    )
    (comp (ref "USB2")
      (value "USB_MICRO_AB")
      (footprint "eagle-import:USB_MICRO_AB")
      (libsource (lib "eagle-import") (part "USB_MICRO_AB"))
    )
    (comp (ref "X1")
      (value "48MHz")
      (footprint "eagle-import:ABM3C")
      (libsource (lib "eagle-import") (part "XTAL-ABRACONABM3C"))
    )
    (comp (ref "X3")
      (value "12MHz")
      (footprint "eagle-import:ABM8G")
      (libsource (lib "eagle-import") (part "XTAL-ABRACONABM8G"))
    )
  )
  (nets
    (net (code "1") (name "/AGND") (class "Default")
      (node (ref "C31") (pin "2") (pinfunction "2_2") (pintype "passive"))
      (node (ref "C33") (pin "2") (pinfunction "2_2") (pintype "passive"))
      (node (ref "C34") (pin "2") (pinfunction "2_2") (pintype "passive"))
      (node (ref "C40") (pin "2") (pinfunction "2_2") (pintype "passive"))
      (node (ref "C41") (pin "2") (pinfunction "2_2") (pintype "passive"))
      (node (ref "C42") (pin "2") (pinfunction "2_2") (pintype "passive"))
      (node (ref "C48") (pin "2") (pinfunction "2_2") (pintype "passive"))
      (node (ref "C50") (pin "2") (pinfunction "2_2") (pintype "passive"))
      (node (ref "LINE_IN") (pin "5") (pinfunction "GND_5") (pintype "bidirectional"))
      (node (ref "PHONE_OUT") (pin "5") (pinfunction "GND_5") (pintype "bidirectional"))
      (node (ref "R17") (pin "2") (pinfunction "2_2") (pintype "passive"))
      (node (ref "R23") (pin "1") (pinfunction "1_1") (pintype "passive"))
      (node (ref "R25") (pin "1") (pinfunction "1_1") (pintype "passive"))
      (node (ref "U3") (pin "17") (pinfunction "AVSS_17") (pintype "bidirectional"))
      (node (ref "U9") (pin "2") (pinfunction "VSS_2") (pintype "bidirectional"))
    )
    (net (code "2") (name "/AUX_VDD") (class "Default")
      (node (ref "C63") (pin "1") (pinfunction "1_1") (pintype "passive"))
      (node (ref "C64") (pin "1") (pinfunction "1_1") (pintype "passive"))
      (node (ref "LED_LL") (pin "2") (pinfunction "A_2") (pintype "passive"))
      (node (ref "LED_LL") (pin "2-2") (pinfunction "A_2-2") (pintype "passive"))
      (node (ref "LED_LR") (pin "2") (pinfunction "A_2") (pintype "passive"))
      (node (ref "LED_LR") (pin "2-2") (pinfunction "A_2-2") (pintype "passive"))
      (node (ref "LED_UL") (pin "2") (pinfunction "A_2") (pintype "passive"))
      (node (ref "LED_UL") (pin "2-2") (pinfunction "A_2-2") (pintype "passive"))
      (node (ref "LED_UR") (pin "2") (pinfunction "A_2") (pintype "passive"))
      (node (ref "LED_UR") (pin "2-2") (pinfunction "A_2-2") (pintype "passive"))
      (node (ref "R36") (pin "2") (pinfunction "2_2") (pintype "passive"))
      (node (ref "TO_MAIN1") (pin "1") (pinfunction "1_1") (pintype "bidirectional"))
      (node (ref "TO_MAIN1") (pin "3") (pinfunction "3_3") (pintype "bidirectional"))
      (node (ref "TO_MAIN1") (pin "5") (pinfunction "5_5") (pintype "bidirectional"))
      (node (ref "TO_MAIN2") (pin "1") (pinfunction "1_1") (pintype "bidirectional"))
      (node (ref "TO_MAIN2") (pin "2") (pinfunction "2_2") (pintype "bidirectional"))
      (node (ref "U8") (pin "18") (pinfunction "VDD_18") (pintype "bidirectional"))
      (node (ref "U8") (pin "4") (pinfunction "VDD_4") (pintype "bidirectional"))
    )
    (net (code "3") (name "/AUX_VSS") (class "Default")
      (node (ref "C63") (pin "2") (pinfunction "2_2") (pintype "passive"))
      (node (ref "C64") (pin "2") (pinfunction "2_2") (pintype "passive"))
      (node (ref "Q2") (pin "2") (pinfunction "S_2") (pintype "passive"))
      (node (ref "Q3") (pin "2") (pinfunction "S_2") (pintype "passive"))
      (node (ref "Q4") (pin "2") (pinfunction "S_2") (pintype "passive"))
      (node (ref "Q5") (pin "2") (pinfunction "S_2") (pintype "passive"))
      (node (ref "Q6") (pin "2") (pinfunction "S_2") (pintype "passive"))
      (node (ref "Q7") (pin "2") (pinfunction "S_2") (pintype "passive"))
      (node (ref "TO_MAIN1") (pin "7") (pinfunction "7_7") (pintype "bidirectional"))
      (node (ref "TO_MAIN1") (pin "9") (pinfunction "9_9") (pintype "bidirectional"))
      (node (ref "TO_MAIN2") (pin "10") (pinfunction "10_10") (pintype "bidirectional"))
      (node (ref "TO_MAIN2") (pin "9") (pinfunction "9_9") (pintype "bidirectional"))
      (node (ref "U8") (pin "21") (pinfunction "VSS_21") (pintype "bidirectional"))
      (node (ref "U8") (pin "5") (pinfunction "VSS_5") (pintype "bidirectional"))
    )
    (net (code "4") (name "/AUX_~{CHANGE}") (class "Default")
      (node (ref "TO_MAIN1") (pin "10") (pinfunction "10_10") (pintype "bidirectional"))
      (node (ref "U8") (pin "28") (pinfunction "~{CHANGE}_28") (pintype "bidirectional"))
    )
    (net (code "5") (name "/AVDD") (class "Default")
      (node (ref "C10") (pin "1") (pinfunction "1_1") (pintype "passive"))
      (node (ref "C11") (pin "1") (pinfunction "1_1") (pintype "passive"))
      (node (ref "C12") (pin "1") (pinfunction "1_1") (pintype "passive"))
      (node (ref "C15") (pin "1") (pinfunction "1_1") (pintype "passive"))
      (node (ref "C16") (pin "1") (pinfunction "1_1") (pintype "passive"))
      (node (ref "C17") (pin "1") (pinfunction "1_1") (pintype "passive"))
      (node (ref "C18") (pin "1") (pinfunction "1_1") (pintype "passive"))
      (node (ref "C19") (pin "1") (pinfunction "1_1") (pintype "passive"))
      (node (ref "C2") (pin "1") (pinfunction "1_1") (pintype "passive"))
      (node (ref "C20") (pin "1") (pinfunction "1_1") (pintype "passive"))
      (node (ref "C21") (pin "1") (pinfunction "1_1") (pintype "passive"))
      (node (ref "C22") (pin "1") (pinfunction "1_1") (pintype "passive"))
      (node (ref "C8") (pin "1") (pinfunction "1_1") (pintype "passive"))
      (node (ref "C9") (pin "1") (pinfunction "1_1") (pintype "passive"))
      (node (ref "L2") (pin "1") (pinfunction "1_1") (pintype "passive"))
      (node (ref "L3") (pin "1") (pinfunction "1_1") (pintype "passive"))
      (node (ref "R9") (pin "2") (pinfunction "2_2") (pintype "passive"))
      (node (ref "U1") (pin "20") (pinfunction "AVDD1_20") (pintype "bidirectional"))
      (node (ref "U1") (pin "23") (pinfunction "AVDD2_23") (pintype "bidirectional"))
      (node (ref "U1") (pin "26") (pinfunction "AVDD3_26") (pintype "bidirectional"))
      (node (ref "U1") (pin "27") (pinfunction "AVDD4_27") (pintype "bidirectional"))
      (node (ref "U1") (pin "28") (pinfunction "AVDD5_28") (pintype "bidirectional"))
      (node (ref "U1") (pin "31") (pinfunction "AVDD6_31") (pintype "bidirectional"))
      (node (ref "U2") (pin "1") (pinfunction "AVDD_PA1_1") (pintype "bidirectional"))
      (node (ref "U2") (pin "10") (pinfunction "AVDD_PA2_10") (pintype "bidirectional"))
      (node (ref "U2") (pin "13") (pinfunction "AVDD_LNA_13") (pintype "bidirectional"))
      (node (ref "U2") (pin "16") (pinfunction "AVDD_BIAS_16") (pintype "bidirectional"))
    )
    (net (code "6") (name "/AVDD_CODEC") (class "Default")
      (node (ref "C31") (pin "1") (pinfunction "1_1") (pintype "passive"))
      (node (ref "C34") (pin "1") (pinfunction "1_1") (pintype "passive"))
      (node (ref "C40") (pin "1") (pinfunction "1_1") (pintype "passive"))
      (node (ref "C41") (pin "1") (pinfunction "1_1") (pintype "passive"))
      (node (ref "C42") (pin "1") (pinfunction "1_1") (pintype "passive"))
      (node (ref "L14") (pin "1") (pinfunction "1_1") (pintype "passive"))
      (node (ref "R22") (pin "2") (pinfunction "2_2") (pintype "passive"))
      (node (ref "R24") (pin "2") (pinfunction "2_2") (pintype "passive"))
      (node (ref "R31") (pin "2") (pinfunction "2_2") (pintype "passive"))
      (node (ref "U3") (pin "26") (pinfunction "LDOIN_26") (pintype "bidirectional"))
      (node (ref "U9") (pin "6") (pinfunction "VDD_6") (pintype "bidirectional"))
    )
    (net (code "7") (name "/AVR_PWR") (class "Default")
      (node (ref "C35") (pin "1") (pinfunction "1_1") (pintype "passive"))
      (node (ref "C46") (pin "1") (pinfunction "1_1") (pintype "passive"))
      (node (ref "C47") (pin "1") (pinfunction "1_1") (pintype "passive"))
      (node (ref "L16") (pin "1") (pinfunction "1_1") (pintype "passive"))
      (node (ref "MICROSD") (pin "VDD") (pinfunction "VDD_VDD") (pintype "bidirectional"))
      (node (ref "R43") (pin "1") (pinfunction "1_1") (pintype "passive"))
      (node (ref "R44") (pin "2") (pinfunction "2_2") (pintype "passive"))
      (node (ref "R6") (pin "1") (pinfunction "1_1") (pintype "passive"))
      (node (ref "U7") (pin "105") (pinfunction "VDDIO_3_105") (pintype "bidirectional"))
      (node (ref "U7") (pin "11") (pinfunction "VDDIO_1_11") (pintype "bidirectional"))
      (node (ref "U7") (pin "125") (pinfunction "VDDIO_4_125") (pintype "bidirectional"))
      (node (ref "U7") (pin "41") (pinfunction "VDDUTMI_41") (pintype "bidirectional"))
      (node (ref "U7") (pin "52") (pinfunction "VDDBU_52") (pintype "bidirectional"))
      (node (ref "U7") (pin "57") (pinfunction "VDDIN_57") (pintype "bidirectional"))
      (node (ref "U7") (pin "62") (pinfunction "VDDIO_2_62") (pintype "bidirectional"))
      (node (ref "U7") (pin "73") (pinfunction "VDDANA_73") (pintype "bidirectional"))
      (node (ref "U7") (pin "75") (pinfunction "ADVREF_75") (pintype "bidirectional"))
    )
    (net (code "8") (name "/DVDD_CODEC") (class "Default")
      (node (ref "C32") (pin "1") (pinfunction "1_1") (pintype "passive"))
      (node (ref "C45") (pin "1") (pinfunction "1_1") (pintype "passive"))
      (node (ref "L15") (pin "1") (pinfunction "1_1") (pintype "passive"))
      (node (ref "U3") (pin "12") (pinfunction "SPI_SELECT_12") (pintype "bidirectional"))
      (node (ref "U3") (pin "30") (pinfunction "LDO_SELECT_30") (pintype "bidirectional"))
      (node (ref "U3") (pin "6") (pinfunction "IOVDD_6") (pintype "bidirectional"))
    )
    (net (code "9") (name "/IOVDD") (class "Default")
      (node (ref "C1") (pin "1") (pinfunction "1_1") (pintype "passive"))
      (node (ref "C3") (pin "1") (pinfunction "1_1") (pintype "passive"))
      (node (ref "C4") (pin "1") (pinfunction "1_1") (pintype "passive"))
      (node (ref "C5") (pin "1") (pinfunction "1_1") (pintype "passive"))
      (node (ref "C6") (pin "1") (pinfunction "1_1") (pintype "passive"))
      (node (ref "C7") (pin "1") (pinfunction "1_1") (pintype "passive"))
      (node (ref "CC8531") (pin "A") (pinfunction "A_A") (pintype "passive"))
      (node (ref "L1") (pin "1") (pinfunction "1_1") (pintype "passive"))
      (node (ref "U1") (pin "10") (pinfunction "IOVDD1_10") (pintype "bidirectional"))
      (node (ref "U1") (pin "12") (pinfunction "IOVDD2_12") (pintype "bidirectional"))
      (node (ref "U1") (pin "18") (pinfunction "IOVDD3_18") (pintype "bidirectional"))
      (node (ref "U1") (pin "37") (pinfunction "IOVDD4_37") (pintype "bidirectional"))
      (node (ref "U1") (pin "40") (pinfunction "DVDD_40") (pintype "bidirectional"))
    )
    (net (code "10") (name "/VBUS") (class "Default")
      (node (ref "C51") (pin "1") (pinfunction "1_1") (pintype "passive"))
      (node (ref "R18") (pin "2") (pinfunction "2_2") (pintype "passive"))
      (node (ref "U6") (pin "11") (pinfunction "VBUS_11") (pintype "bidirectional"))
      (node (ref "U6") (pin "13") (pinfunction "D0_13") (pintype "bidirectional"))
      (node (ref "U7") (pin "39") (pinfunction "VBUS_39") (pintype "bidirectional"))
      (node (ref "USB1") (pin "1") (pinfunction "VBUS_1") (pintype "bidirectional"))
      (node (ref "USB2") (pin "1") (pinfunction "VBUS_1") (pintype "bidirectional"))
    )
    (net (code "11") (name "/VDDCORE") (class "Default")
      (node (ref "C43") (pin "1") (pinfunction "1_1") (pintype "passive"))
      (node (ref "C44") (pin "1") (pinfunction "1_1") (pintype "passive"))
      (node (ref "U7") (pin "10") (pinfunction "VDDCORE_1_10") (pintype "bidirectional"))
      (node (ref "U7") (pin "104") (pinfunction "VDDCORE_4_104") (pintype "bidirectional"))
      (node (ref "U7") (pin "124") (pinfunction "VDDCORE_5_124") (pintype "bidirectional"))
      (node (ref "U7") (pin "34") (pinfunction "VDDPLL_34") (pintype "bidirectional"))
      (node (ref "U7") (pin "45") (pinfunction "VDDCORE_2_45") (pintype "bidirectional"))
      (node (ref "U7") (pin "56") (pinfunction "VDDOUT_56") (pintype "bidirectional"))
      (node (ref "U7") (pin "61") (pinfunction "VDDCORE_3_61") (pintype "bidirectional"))
    )
    (net (code "12") (name "/~{AVR_LED}") (class "Default")
      (node (ref "AVR") (pin "C") (pinfunction "C_C") (pintype "passive"))
      (node (ref "U7") (pin "72") (pinfunction "PA20_72") (pintype "bidirectional"))
    )
    (net (code "13") (name "/~{CHANGE}") (class "Default")
      (node (ref "TO_AUX1") (pin "9") (pinfunction "9_9") (pintype "bidirectional"))
      (node (ref "U7") (pin "32") (pinfunction "PD10_32") (pintype "bidirectional"))
    )
    (net (code "14") (name "/~{PAIR}") (class "Default")
      (node (ref "U1") (pin "7") (pinfunction "GIO1_7") (pintype "bidirectional"))
      (node (ref "U7") (pin "21") (pinfunction "PD8_21") (pintype "bidirectional"))
    )
    (net (code "15") (name "/~{RESET}") (class "Default")
      (node (ref "U7") (pin "47") (pinfunction "NRSTB_47") (pintype "bidirectional"))
    )
    (net (code "16") (name "/~{SD_CARD}") (class "Default")
      (node (ref "MICROSD") (pin "SWA") (pinfunction "SWA_SWA") (pintype "bidirectional"))
      (node (ref "R6") (pin "2") (pinfunction "2_2") (pintype "passive"))
      (node (ref "U7") (pin "67") (pinfunction "PC9_67") (pintype "bidirectional"))
    )
    (net (code "17") (name "3.3V") (class "Default")
      (node (ref "C53") (pin "1") (pinfunction "1_1") (pintype "passive"))
      (node (ref "CCD") (pin "2") (pinfunction "2_2") (pintype "bidirectional"))
      (node (ref "EXT") (pin "2") (pinfunction "2_2") (pintype "passive"))
      (node (ref "L1") (pin "2") (pinfunction "2_2") (pintype "passive"))
      (node (ref "L14") (pin "2") (pinfunction "2_2") (pintype "passive"))
      (node (ref "L15") (pin "2") (pinfunction "2_2") (pintype "passive"))
      (node (ref "L16") (pin "2") (pinfunction "2_2") (pintype "passive"))
      (node (ref "L18") (pin "2") (pinfunction "2_2") (pintype "passive"))
      (node (ref "L19") (pin "2") (pinfunction "2_2") (pintype "passive"))
      (node (ref "L2") (pin "2") (pinfunction "2_2") (pintype "passive"))
      (node (ref "L3") (pin "2") (pinfunction "2_2") (pintype "passive"))
      (node (ref "R3") (pin "2") (pinfunction "2_2") (pintype "passive"))
      (node (ref "U5") (pin "3") (pinfunction "VOUT_3") (pintype "bidirectional"))
    )
    (net (code "18") (name "AUDIO") (class "Default")
      (node (ref "C36") (pin "1") (pinfunction "1_1") (pintype "passive"))
      (node (ref "R12") (pin "1") (pinfunction "1_1") (pintype "passive"))
      (node (ref "U7") (pin "85") (pinfunction "PA2_85") (pintype "bidirectional"))
      (node (ref "U9") (pin "7") (pinfunction "OUTA_7") (pintype "bidirectional"))
    )
    (net (code "19") (name "AUX_BLUE_BOT") (class "Default")
      (node (ref "Q7") (pin "1") (pinfunction "G_1") (pintype "passive"))
      (node (ref "TO_MAIN2") (pin "7") (pinfunction "7_7") (pintype "bidirectional"))
    )
    (net (code "20") (name "AUX_BLUE_TOP") (class "Default")
      (node (ref "Q4") (pin "1") (pinfunction "G_1") (pintype "passive"))
      (node (ref "TO_MAIN2") (pin "4") (pinfunction "4_4") (pintype "bidirectional"))
    )
    (net (code "21") (name "AUX_CS") (class "Default")
      (node (ref "TO_MAIN1") (pin "8") (pinfunction "8_8") (pintype "bidirectional"))
      (node (ref "U8") (pin "14") (pinfunction "~{SS}_14") (pintype "bidirectional"))
    )
    (net (code "22") (name "AUX_GREEN_BOT") (class "Default")
      (node (ref "Q6") (pin "1") (pinfunction "G_1") (pintype "passive"))
      (node (ref "TO_MAIN2") (pin "5") (pinfunction "5_5") (pintype "bidirectional"))
    )
    (net (code "23") (name "AUX_GREEN_TOP") (class "Default")
      (node (ref "Q3") (pin "1") (pinfunction "G_1") (pintype "passive"))
      (node (ref "TO_MAIN2") (pin "6") (pinfunction "6_6") (pintype "bidirectional"))
    )
    (net (code "24") (name "AUX_MISO") (class "Default")
      (node (ref "TO_MAIN1") (pin "4") (pinfunction "4_4") (pintype "bidirectional"))
      (node (ref "U8") (pin "16") (pinfunction "MISO_16") (pintype "bidirectional"))
    )
    (net (code "25") (name "AUX_MOSI") (class "Default")
      (node (ref "TO_MAIN1") (pin "6") (pinfunction "6_6") (pintype "bidirectional"))
      (node (ref "U8") (pin "15") (pinfunction "MOSI_15") (pintype "bidirectional"))
    )
    (net (code "26") (name "AUX_RED_BOT") (class "Default")
      (node (ref "Q5") (pin "1") (pinfunction "G_1") (pintype "passive"))
      (node (ref "TO_MAIN2") (pin "3") (pinfunction "3_3") (pintype "bidirectional"))
    )
    (net (code "27") (name "AUX_RED_TOP") (class "Default")
      (node (ref "Q2") (pin "1") (pinfunction "G_1") (pintype "passive"))
      (node (ref "TO_MAIN2") (pin "8") (pinfunction "8_8") (pintype "bidirectional"))
    )
    (net (code "28") (name "AUX_SCLK") (class "Default")
      (node (ref "TO_MAIN1") (pin "2") (pinfunction "2_2") (pintype "bidirectional"))
      (node (ref "U8") (pin "17") (pinfunction "SCK_17") (pintype "bidirectional"))
    )
    (net (code "29") (name "BCLK") (class "Default")
      (node (ref "L6") (pin "1") (pinfunction "1_1") (pintype "passive"))
      (node (ref "U3") (pin "2") (pinfunction "BCLK_2") (pintype "bidirectional"))
    )
    (net (code "30") (name "BLUE_BOT") (class "Default")
      (node (ref "TO_AUX2") (pin "8") (pinfunction "8_8") (pintype "bidirectional"))
      (node (ref "U7") (pin "135") (pinfunction "PC24_135") (pintype "bidirectional"))
    )
    (net (code "31") (name "BLUE_TOP") (class "Default")
      (node (ref "TO_AUX2") (pin "3") (pinfunction "3_3") (pintype "bidirectional"))
      (node (ref "U7") (pin "134") (pinfunction "PC23_134") (pintype "bidirectional"))
    )
    (net (code "32") (name "CS_CC8531") (class "Default")
      (node (ref "CCD") (pin "5") (pinfunction "5_5") (pintype "bidirectional"))
      (node (ref "U1") (pin "3") (pinfunction "CSN_3") (pintype "bidirectional"))
      (node (ref "U7") (pin "22") (pinfunction "PD9_22") (pintype "bidirectional"))
    )
    (net (code "33") (name "CS_CODEC") (class "Default")
      (node (ref "U3") (pin "9") (pinfunction "SCL/SSZ_9") (pintype "bidirectional"))
      (node (ref "U7") (pin "15") (pinfunction "PD2_15") (pintype "bidirectional"))
    )
    (net (code "34") (name "CS_SD") (class "Default")
      (node (ref "MICROSD") (pin "CD/DAT3") (pinfunction "~{CS}_CD/DAT3") (pintype "bidirectional"))
      (node (ref "U7") (pin "66") (pinfunction "PC8_66") (pintype "bidirectional"))
    )
    (net (code "35") (name "CS_TOUCH") (class "Default")
      (node (ref "TO_AUX1") (pin "7") (pinfunction "7_7") (pintype "bidirectional"))
      (node (ref "U7") (pin "26") (pinfunction "PA7_26") (pintype "bidirectional"))
    )
    (net (code "36") (name "D+_CC8531") (class "Default")
      (node (ref "R2") (pin "2") (pinfunction "2_2") (pintype "passive"))
      (node (ref "R7") (pin "2") (pinfunction "2_2") (pintype "passive"))
      (node (ref "USB1") (pin "3") (pinfunction "D+_3") (pintype "bidirectional"))
    )
    (net (code "37") (name "D+_UC") (class "Default")
      (node (ref "R42") (pin "2") (pinfunction "2_2") (pintype "passive"))
      (node (ref "U7") (pin "37") (pinfunction "DHSDP_37") (pintype "bidirectional"))
      (node (ref "USB2") (pin "3") (pinfunction "D+_3") (pintype "bidirectional"))
    )
    (net (code "38") (name "D-_CC8531") (class "Default")
      (node (ref "R1") (pin "2") (pinfunction "2_2") (pintype "passive"))
      (node (ref "USB1") (pin "2") (pinfunction "D-_2") (pintype "bidirectional"))
    )
    (net (code "39") (name "D-_UC") (class "Default")
      (node (ref "R41") (pin "2") (pinfunction "2_2") (pintype "passive"))
      (node (ref "U7") (pin "38") (pinfunction "DHSDM_38") (pintype "bidirectional"))
      (node (ref "USB2") (pin "2") (pinfunction "D-_2") (pintype "bidirectional"))
    )
    (net (code "40") (name "DIN") (class "Default")
      (node (ref "L13") (pin "1") (pinfunction "1_1") (pintype "passive"))
      (node (ref "U3") (pin "4") (pinfunction "DIN/MFP1_4") (pintype "bidirectional"))
    )
    (net (code "41") (name "DOUT") (class "Default")
      (node (ref "L11") (pin "1") (pinfunction "1_1") (pintype "passive"))
      (node (ref "U3") (pin "5") (pinfunction "DOUT/MFP2_5") (pintype "bidirectional"))
    )
    (net (code "42") (name "ERASE") (class "Default")
      (node (ref "U7") (pin "130") (pinfunction "PC0_130") (pintype "bidirectional"))
    )
    (net (code "43") (name "GND") (class "Default")
      (node (ref "BATTERY") (pin "-") (pinfunction "N_-") (pintype "passive"))
      (node (ref "BATTERY") (pin "X1") (pinfunction "CASE_X1") (pintype "passive"))
      (node (ref "BATTERY") (pin "X2") (pinfunction "CASE_X2") (pintype "passive"))
      (node (ref "C1") (pin "2") (pinfunction "2_2") (pintype "passive"))
      (node (ref "C10") (pin "2") (pinfunction "2_2") (pintype "passive"))
      (node (ref "C11") (pin "2") (pinfunction "2_2") (pintype "passive"))
      (node (ref "C12") (pin "2") (pinfunction "2_2") (pintype "passive"))
      (node (ref "C13") (pin "2") (pinfunction "2_2") (pintype "passive"))
      (node (ref "C14") (pin "2") (pinfunction "2_2") (pintype "passive"))
      (node (ref "C15") (pin "2") (pinfunction "2_2") (pintype "passive"))
      (node (ref "C16") (pin "2") (pinfunction "2_2") (pintype "passive"))
      (node (ref "C17") (pin "2") (pinfunction "2_2") (pintype "passive"))
      (node (ref "C18") (pin "2") (pinfunction "2_2") (pintype "passive"))
      (node (ref "C19") (pin "2") (pinfunction "2_2") (pintype "passive"))
      (node (ref "C2") (pin "2") (pinfunction "2_2") (pintype "passive"))
      (node (ref "C20") (pin "2") (pinfunction "2_2") (pintype "passive"))
      (node (ref "C21") (pin "2") (pinfunction "2_2") (pintype "passive"))
      (node (ref "C22") (pin "2") (pinfunction "2_2") (pintype "passive"))
      (node (ref "C23") (pin "2") (pinfunction "2_2") (pintype "passive"))
      (node (ref "C24") (pin "2") (pinfunction "2_2") (pintype "passive"))
      (node (ref "C27") (pin "2") (pinfunction "2_2") (pintype "passive"))
      (node (ref "C28") (pin "2") (pinfunction "2_2") (pintype "passive"))
      (node (ref "C29") (pin "2") (pinfunction "2_2") (pintype "passive"))
      (node (ref "C3") (pin "2") (pinfunction "2_2") (pintype "passive"))
      (node (ref "C30") (pin "2") (pinfunction "2_2") (pintype "passive"))
      (node (ref "C32") (pin "2") (pinfunction "2_2") (pintype "passive"))
      (node (ref "C35") (pin "2") (pinfunction "2_2") (pintype "passive"))
      (node (ref "C4") (pin "2") (pinfunction "2_2") (pintype "passive"))
      (node (ref "C43") (pin "2") (pinfunction "2_2") (pintype "passive"))
      (node (ref "C44") (pin "2") (pinfunction "2_2") (pintype "passive"))
      (node (ref "C45") (pin "2") (pinfunction "2_2") (pintype "passive"))
      (node (ref "C46") (pin "2") (pinfunction "2_2") (pintype "passive"))
      (node (ref "C47") (pin "2") (pinfunction "2_2") (pintype "passive"))
      (node (ref "C49") (pin "2") (pinfunction "2_2") (pintype "passive"))
      (node (ref "C5") (pin "2") (pinfunction "2_2") (pintype "passive"))
      (node (ref "C51") (pin "2") (pinfunction "2_2") (pintype "passive"))
      (node (ref "C52") (pin "2") (pinfunction "2_2") (pintype "passive"))
      (node (ref "C53") (pin "2") (pinfunction "2_2") (pintype "passive"))
      (node (ref "C54") (pin "2") (pinfunction "2_2") (pintype "passive"))
      (node (ref "C56") (pin "2") (pinfunction "2_2") (pintype "passive"))
      (node (ref "C57") (pin "2") (pinfunction "2_2") (pintype "passive"))
      (node (ref "C6") (pin "2") (pinfunction "2_2") (pintype "passive"))
      (node (ref "C65") (pin "2") (pinfunction "2_2") (pintype "passive"))
      (node (ref "C68") (pin "2") (pinfunction "2_2") (pintype "passive"))
      (node (ref "C7") (pin "2") (pinfunction "2_2") (pintype "passive"))
      (node (ref "C8") (pin "2") (pinfunction "2_2") (pintype "passive"))
      (node (ref "C9") (pin "2") (pinfunction "2_2") (pintype "passive"))
      (node (ref "CCD") (pin "1") (pinfunction "1_1") (pintype "bidirectional"))
      (node (ref "L10") (pin "1") (pinfunction "1_1") (pintype "passive"))
      (node (ref "MICROSD") (pin "GND1") (pinfunction "GND_GND1") (pintype "bidirectional"))
      (node (ref "MICROSD") (pin "GND2") (pinfunction "GND_GND2") (pintype "bidirectional"))
      (node (ref "MICROSD") (pin "GND3") (pinfunction "GND_GND3") (pintype "bidirectional"))
      (node (ref "MICROSD") (pin "GND4") (pinfunction "GND_GND4") (pintype "bidirectional"))
      (node (ref "MICROSD") (pin "SWB") (pinfunction "SWB_SWB") (pintype "bidirectional"))
      (node (ref "MICROSD") (pin "VSS") (pinfunction "GND_VSS") (pintype "bidirectional"))
      (node (ref "POWER") (pin "C") (pinfunction "C_C") (pintype "passive"))
      (node (ref "R10") (pin "1") (pinfunction "1_1") (pintype "passive"))
      (node (ref "R17") (pin "1") (pinfunction "1_1") (pintype "passive"))
      (node (ref "R20") (pin "1") (pinfunction "1_1") (pintype "passive"))
      (node (ref "R21") (pin "1") (pinfunction "1_1") (pintype "passive"))
      (node (ref "R32") (pin "1") (pinfunction "1_1") (pintype "passive"))
      (node (ref "R4") (pin "1") (pinfunction "1_1") (pintype "passive"))
      (node (ref "R8") (pin "1") (pinfunction "1_1") (pintype "passive"))
      (node (ref "SMA") (pin "GND1") (pinfunction "GND_GND1") (pintype "bidirectional"))
      (node (ref "SMA") (pin "GND2") (pinfunction "GND_GND2") (pintype "bidirectional"))
      (node (ref "SMA") (pin "GND3") (pinfunction "GND_GND3") (pintype "bidirectional"))
      (node (ref "SMA") (pin "GND4") (pinfunction "GND_GND4") (pintype "bidirectional"))
      (node (ref "TO_AUX1") (pin "10") (pinfunction "10_10") (pintype "bidirectional"))
      (node (ref "TO_AUX1") (pin "6") (pinfunction "6_6") (pintype "bidirectional"))
      (node (ref "TO_AUX1") (pin "8") (pinfunction "8_8") (pintype "bidirectional"))
      (node (ref "TO_AUX2") (pin "10") (pinfunction "10_10") (pintype "bidirectional"))
      (node (ref "TO_AUX2") (pin "9") (pinfunction "9_9") (pintype "bidirectional"))
      (node (ref "U1") (pin "29") (pinfunction "VBAT_29") (pintype "bidirectional"))
      (node (ref "U1") (pin "34") (pinfunction "GIO12_34") (pintype "bidirectional"))
      (node (ref "U1") (pin "35") (pinfunction "GIO13_35") (pintype "bidirectional"))
      (node (ref "U1") (pin "8") (pinfunction "GIO2_8") (pintype "bidirectional"))
      (node (ref "U1") (pin "GND") (pinfunction "GND_GND") (pintype "bidirectional"))
      (node (ref "U2") (pin "12") (pinfunction "GND_12") (pintype "bidirectional"))
      (node (ref "U2") (pin "14") (pinfunction "GND_14") (pintype "bidirectional"))
      (node (ref "U2") (pin "8") (pinfunction "GND_8") (pintype "bidirectional"))
      (node (ref "U2") (pin "9") (pinfunction "GND_9") (pintype "bidirectional"))
      (node (ref "U2") (pin "GND") (pinfunction "GND_GND") (pintype "bidirectional"))
      (node (ref "U3") (pin "28") (pinfunction "DVSS_28") (pintype "bidirectional"))
      (node (ref "U3") (pin "7") (pinfunction "IOVSS_7") (pintype "bidirectional"))
      (node (ref "U3") (pin "GND") (pinfunction "GND_GND") (pintype "bidirectional"))
      (node (ref "U5") (pin "2") (pinfunction "GND_2") (pintype "bidirectional"))
      (node (ref "U5") (pin "4") (pinfunction "GND_4") (pintype "bidirectional"))
      (node (ref "U6") (pin "1") (pinfunction "NTC_1") (pintype "bidirectional"))
      (node (ref "U6") (pin "14") (pinfunction "D1_14") (pintype "bidirectional"))
      (node (ref "U6") (pin "4") (pinfunction "D2_4") (pintype "bidirectional"))
      (node (ref "U6") (pin "GND") (pinfunction "GND_GND") (pintype "bidirectional"))
      (node (ref "U7") (pin "106") (pinfunction "GND_3_106") (pintype "bidirectional"))
      (node (ref "U7") (pin "12") (pinfunction "GND_1_12") (pintype "bidirectional"))
      (node (ref "U7") (pin "126") (pinfunction "GND_4_126") (pintype "bidirectional"))
      (node (ref "U7") (pin "33") (pinfunction "GNDPLL_33") (pintype "bidirectional"))
      (node (ref "U7") (pin "44") (pinfunction "GNDUTMI_44") (pintype "bidirectional"))
      (node (ref "U7") (pin "46") (pinfunction "JTAGSEL_46") (pintype "bidirectional"))
      (node (ref "U7") (pin "54") (pinfunction "GNDBU_54") (pintype "bidirectional"))
      (node (ref "U7") (pin "58") (pinfunction "GND_2_58") (pintype "bidirectional"))
      (node (ref "U7") (pin "74") (pinfunction "GNDANA_74") (pintype "bidirectional"))
      (node (ref "USB1") (pin "5") (pinfunction "GND_5") (pintype "bidirectional"))
      (node (ref "USB1") (pin "GND1") (pinfunction "GND_GND1") (pintype "bidirectional"))
      (node (ref "USB1") (pin "GND2") (pinfunction "GND_GND2") (pintype "bidirectional"))
      (node (ref "USB1") (pin "GND3") (pinfunction "GND_GND3") (pintype "bidirectional"))
      (node (ref "USB1") (pin "GND4") (pinfunction "GND_GND4") (pintype "bidirectional"))
      (node (ref "USB2") (pin "5") (pinfunction "GND_5") (pintype "bidirectional"))
      (node (ref "USB2") (pin "GND1") (pinfunction "GND_GND1") (pintype "bidirectional"))
      (node (ref "USB2") (pin "GND2") (pinfunction "GND_GND2") (pintype "bidirectional"))
      (node (ref "USB2") (pin "GND3") (pinfunction "GND_GND3") (pintype "bidirectional"))
      (node (ref "USB2") (pin "GND4") (pinfunction "GND_GND4") (pintype "bidirectional"))
      (node (ref "X1") (pin "2") (pinfunction "CASE_2") (pintype "passive"))
      (node (ref "X1") (pin "4") (pinfunction "CASE_4") (pintype "passive"))
      (node (ref "X3") (pin "GND-1") (pinfunction "CASE_GND-1") (pintype "passive"))
      (node (ref "X3") (pin "GND-2") (pinfunction "CASE_GND-2") (pintype "passive"))
    )
    (net (code "44") (name "GREEN_BOT") (class "Default")
      (node (ref "TO_AUX2") (pin "6") (pinfunction "6_6") (pintype "bidirectional"))
      (node (ref "U7") (pin "136") (pinfunction "PC25_136") (pintype "bidirectional"))
    )
    (net (code "45") (name "GREEN_TOP") (class "Default")
      (node (ref "TO_AUX2") (pin "5") (pinfunction "5_5") (pintype "bidirectional"))
      (node (ref "U7") (pin "133") (pinfunction "PC22_133") (pintype "bidirectional"))
    )
    (net (code "46") (name "IN_L") (class "Default")
      (node (ref "C38") (pin "1") (pinfunction "1_1") (pintype "passive"))
      (node (ref "LINE_IN") (pin "4") (pinfunction "L_4") (pintype "bidirectional"))
      (node (ref "R23") (pin "2") (pinfunction "2_2") (pintype "passive"))
    )
    (net (code "47") (name "IN_R") (class "Default")
      (node (ref "C37") (pin "1") (pinfunction "1_1") (pintype "passive"))
      (node (ref "LINE_IN") (pin "1") (pinfunction "R_1") (pintype "bidirectional"))
    )
    (net (code "48") (name "LINEIN_SENSE") (class "Default")
      (node (ref "LINE_IN") (pin "3") (pinfunction "L_SW_3") (pintype "bidirectional"))
      (node (ref "R22") (pin "1") (pinfunction "1_1") (pintype "passive"))
      (node (ref "U7") (pin "101") (pinfunction "PC19_101") (pintype "bidirectional"))
    )
    (net (code "49") (name "LINE_L") (class "Default")
      (node (ref "R27") (pin "1") (pinfunction "1_1") (pintype "passive"))
      (node (ref "U3") (pin "22") (pinfunction "LOL_22") (pintype "bidirectional"))
    )
    (net (code "50") (name "LINE_R") (class "Default")
      (node (ref "R29") (pin "1") (pinfunction "1_1") (pintype "passive"))
      (node (ref "U3") (pin "23") (pinfunction "LOR_23") (pintype "bidirectional"))
    )
    (net (code "51") (name "LNA_EN") (class "Default")
      (node (ref "U1") (pin "38") (pinfunction "XLNAEN_38") (pintype "bidirectional"))
      (node (ref "U2") (pin "6") (pinfunction "EN_6") (pintype "bidirectional"))
    )
    (net (code "52") (name "MCLK") (class "Default")
      (node (ref "L5") (pin "1") (pinfunction "1_1") (pintype "passive"))
      (node (ref "U3") (pin "1") (pinfunction "MCLK_1") (pintype "bidirectional"))
    )
    (net (code "53") (name "MISO") (class "Default")
      (node (ref "CCD") (pin "10") (pinfunction "10_10") (pintype "bidirectional"))
      (node (ref "MICROSD") (pin "DAT0") (pinfunction "MISO_DAT0") (pintype "bidirectional"))
      (node (ref "TO_AUX1") (pin "3") (pinfunction "3_3") (pintype "bidirectional"))
      (node (ref "U1") (pin "6") (pinfunction "MISO_6") (pintype "bidirectional"))
      (node (ref "U3") (pin "11") (pinfunction "MISO/MFP4_11") (pintype "bidirectional"))
      (node (ref "U7") (pin "108") (pinfunction "PA25_108") (pintype "bidirectional"))
    )
    (net (code "54") (name "MOSI") (class "Default")
      (node (ref "CCD") (pin "8") (pinfunction "8_8") (pintype "bidirectional"))
      (node (ref "MICROSD") (pin "CMD") (pinfunction "MOSI_CMD") (pintype "bidirectional"))
      (node (ref "TO_AUX1") (pin "5") (pinfunction "5_5") (pintype "bidirectional"))
      (node (ref "U1") (pin "5") (pinfunction "MOSI_5") (pintype "bidirectional"))
      (node (ref "U3") (pin "10") (pinfunction "SDA/MOSI_10") (pintype "bidirectional"))
      (node (ref "U7") (pin "109") (pinfunction "PA26_109") (pintype "bidirectional"))
    )
    (net (code "55") (name "Net-(AVR-PadA)") (class "Default")
      (node (ref "AVR") (pin "A") (pinfunction "A_A") (pintype "passive"))
      (node (ref "R44") (pin "1") (pinfunction "1_1") (pintype "passive"))
    )
    (net (code "56") (name "Net-(BATTERY-P)") (class "Default")
      (node (ref "BATTERY") (pin "+") (pinfunction "P_+") (pintype "passive"))
      (node (ref "Q1") (pin "2") (pinfunction "S_2") (pintype "passive"))
      (node (ref "U6") (pin "9") (pinfunction "BAT_9") (pintype "bidirectional"))
    )
    (net (code "57") (name "Net-(C25-Pad1)") (class "Default")
      (node (ref "C25") (pin "1") (pinfunction "1_1") (pintype "passive"))
      (node (ref "L8") (pin "2") (pinfunction "2_2") (pintype "passive"))
    )
    (net (code "58") (name "Net-(C25-Pad2)") (class "Default")
      (node (ref "C25") (pin "2") (pinfunction "2_2") (pintype "passive"))
      (node (ref "C26") (pin "1") (pinfunction "1_1") (pintype "passive"))
      (node (ref "C28") (pin "1") (pinfunction "1_1") (pintype "passive"))
      (node (ref "L10") (pin "2") (pinfunction "2_2") (pintype "passive"))
    )
    (net (code "59") (name "Net-(C26-Pad2)") (class "Default")
      (node (ref "C26") (pin "2") (pinfunction "2_2") (pintype "passive"))
      (node (ref "SMA") (pin "SIG") (pinfunction "SIG_SIG") (pintype "bidirectional"))
    )
    (net (code "60") (name "Net-(C27-Pad1)") (class "Default")
      (node (ref "C27") (pin "1") (pinfunction "1_1") (pintype "passive"))
      (node (ref "L7") (pin "2") (pinfunction "2_2") (pintype "passive"))
      (node (ref "L8") (pin "1") (pinfunction "1_1") (pintype "passive"))
    )
    (net (code "61") (name "Net-(C54-Pad1)") (class "Default")
      (node (ref "C54") (pin "1") (pinfunction "1_1") (pintype "passive"))
      (node (ref "R19") (pin "1") (pinfunction "1_1") (pintype "passive"))
    )
    (net (code "62") (name "Net-(C57-Pad1)") (class "Default")
      (node (ref "C57") (pin "1") (pinfunction "1_1") (pintype "passive"))
      (node (ref "L19") (pin "1") (pinfunction "1_1") (pintype "passive"))
      (node (ref "TO_AUX2") (pin "1") (pinfunction "1_1") (pintype "bidirectional"))
      (node (ref "TO_AUX2") (pin "2") (pinfunction "2_2") (pintype "bidirectional"))
    )
    (net (code "63") (name "Net-(C65-Pad1)") (class "Default")
      (node (ref "C65") (pin "1") (pinfunction "1_1") (pintype "passive"))
      (node (ref "L18") (pin "1") (pinfunction "1_1") (pintype "passive"))
      (node (ref "TO_AUX1") (pin "2") (pinfunction "2_2") (pintype "bidirectional"))
      (node (ref "TO_AUX1") (pin "4") (pinfunction "4_4") (pintype "bidirectional"))
    )
    (net (code "64") (name "Net-(CC8531-PadC)") (class "Default")
      (node (ref "CC8531") (pin "C") (pinfunction "C_C") (pintype "passive"))
      (node (ref "R5") (pin "2") (pinfunction "2_2") (pintype "passive"))
    )
    (net (code "65") (name "Net-(CCD-Pad9)") (class "Default")
      (node (ref "CCD") (pin "9") (pinfunction "9_9") (pintype "bidirectional"))
      (node (ref "EXT") (pin "1") (pinfunction "1_1") (pintype "passive"))
    )
    (net (code "66") (name "Net-(CHARGE-PadA)") (class "Default")
      (node (ref "CHARGE") (pin "A") (pinfunction "A_A") (pintype "passive"))
      (node (ref "R18") (pin "1") (pinfunction "1_1") (pintype "passive"))
    )
    (net (code "67") (name "Net-(POWER-PadA)") (class "Default")
      (node (ref "POWER") (pin "A") (pinfunction "A_A") (pintype "passive"))
      (node (ref "R3") (pin "1") (pinfunction "1_1") (pintype "passive"))
    )
    (net (code "68") (name "Net-(Q1-D)") (class "Default")
      (node (ref "C52") (pin "1") (pinfunction "1_1") (pintype "passive"))
      (node (ref "F1") (pin "1") (pinfunction "1_1") (pintype "passive"))
      (node (ref "L17") (pin "2") (pinfunction "2_2") (pintype "passive"))
      (node (ref "Q1") (pin "3") (pinfunction "D_3") (pintype "passive"))
      (node (ref "U6") (pin "10") (pinfunction "VOUT_10") (pintype "bidirectional"))
      (node (ref "U6") (pin "3") (pinfunction "VOUTS_3") (pintype "bidirectional"))
    )
    (net (code "69") (name "Net-(Q1-G)") (class "Default")
      (node (ref "Q1") (pin "1") (pinfunction "G_1") (pintype "passive"))
      (node (ref "U6") (pin "8") (pinfunction "GATE_8") (pintype "bidirectional"))
    )
    (net (code "70") (name "Net-(Q2-D)") (class "Default")
      (node (ref "LED_UL") (pin "1") (pinfunction "KR_1") (pintype "passive"))
      (node (ref "LED_UL") (pin "1-2") (pinfunction "KR_1-2") (pintype "passive"))
      (node (ref "LED_UR") (pin "1") (pinfunction "KR_1") (pintype "passive"))
      (node (ref "LED_UR") (pin "1-2") (pinfunction "KR_1-2") (pintype "passive"))
      (node (ref "Q2") (pin "3") (pinfunction "D_3") (pintype "passive"))
    )
    (net (code "71") (name "Net-(Q3-D)") (class "Default")
      (node (ref "LED_UL") (pin "4") (pinfunction "KG_4") (pintype "passive"))
      (node (ref "LED_UL") (pin "4-2") (pinfunction "KG_4-2") (pintype "passive"))
      (node (ref "LED_UR") (pin "4") (pinfunction "KG_4") (pintype "passive"))
      (node (ref "LED_UR") (pin "4-2") (pinfunction "KG_4-2") (pintype "passive"))
      (node (ref "Q3") (pin "3") (pinfunction "D_3") (pintype "passive"))
    )
    (net (code "72") (name "Net-(Q4-D)") (class "Default")
      (node (ref "LED_UL") (pin "3") (pinfunction "KB_3") (pintype "passive"))
      (node (ref "LED_UL") (pin "3-2") (pinfunction "KB_3-2") (pintype "passive"))
      (node (ref "LED_UR") (pin "3") (pinfunction "KB_3") (pintype "passive"))
      (node (ref "LED_UR") (pin "3-2") (pinfunction "KB_3-2") (pintype "passive"))
      (node (ref "Q4") (pin "3") (pinfunction "D_3") (pintype "passive"))
    )
    (net (code "73") (name "Net-(Q5-D)") (class "Default")
      (node (ref "LED_LL") (pin "1") (pinfunction "KR_1") (pintype "passive"))
      (node (ref "LED_LL") (pin "1-2") (pinfunction "KR_1-2") (pintype "passive"))
      (node (ref "LED_LR") (pin "1") (pinfunction "KR_1") (pintype "passive"))
      (node (ref "LED_LR") (pin "1-2") (pinfunction "KR_1-2") (pintype "passive"))
      (node (ref "Q5") (pin "3") (pinfunction "D_3") (pintype "passive"))
    )
    (net (code "74") (name "Net-(Q6-D)") (class "Default")
      (node (ref "LED_LL") (pin "4") (pinfunction "KG_4") (pintype "passive"))
      (node (ref "LED_LL") (pin "4-2") (pinfunction "KG_4-2") (pintype "passive"))
      (node (ref "LED_LR") (pin "4") (pinfunction "KG_4") (pintype "passive"))
      (node (ref "LED_LR") (pin "4-2") (pinfunction "KG_4-2") (pintype "passive"))
      (node (ref "Q6") (pin "3") (pinfunction "D_3") (pintype "passive"))
    )
    (net (code "75") (name "Net-(Q7-D)") (class "Default")
      (node (ref "LED_LL") (pin "3") (pinfunction "KB_3") (pintype "passive"))
      (node (ref "LED_LL") (pin "3-2") (pinfunction "KB_3-2") (pintype "passive"))
      (node (ref "LED_LR") (pin "3") (pinfunction "KB_3") (pintype "passive"))
      (node (ref "LED_LR") (pin "3-2") (pinfunction "KB_3-2") (pintype "passive"))
      (node (ref "Q7") (pin "3") (pinfunction "D_3") (pintype "passive"))
    )
    (net (code "76") (name "Net-(R13-Pad2)") (class "Default")
      (node (ref "R13") (pin "2") (pinfunction "2_2") (pintype "passive"))
      (node (ref "R27") (pin "2") (pinfunction "2_2") (pintype "passive"))
      (node (ref "R28") (pin "2") (pinfunction "2_2") (pintype "passive"))
    )
    (net (code "77") (name "Net-(R16-Pad2)") (class "Default")
      (node (ref "R16") (pin "2") (pinfunction "2_2") (pintype "passive"))
      (node (ref "R29") (pin "2") (pinfunction "2_2") (pintype "passive"))
      (node (ref "R30") (pin "2") (pinfunction "2_2") (pintype "passive"))
    )
    (net (code "78") (name "Net-(R26-Pad2)") (class "Default")
      (node (ref "R26") (pin "2") (pinfunction "2_2") (pintype "passive"))
      (node (ref "SW1") (pin "P$1") (pinfunction "P$1_P$1") (pintype "bidirectional"))
    )
    (net (code "79") (name "Net-(R33-Pad2)") (class "Default")
      (node (ref "R33") (pin "2") (pinfunction "2_2") (pintype "passive"))
      (node (ref "SW4") (pin "P$1") (pinfunction "P$1_P$1") (pintype "bidirectional"))
    )
    (net (code "80") (name "Net-(R34-Pad2)") (class "Default")
      (node (ref "R34") (pin "2") (pinfunction "2_2") (pintype "passive"))
      (node (ref "SW5") (pin "P$1") (pinfunction "P$1_P$1") (pintype "bidirectional"))
    )
    (net (code "81") (name "Net-(R35-Pad2)") (class "Default")
      (node (ref "R35") (pin "2") (pinfunction "2_2") (pintype "passive"))
      (node (ref "SW6") (pin "P$1") (pinfunction "P$1_P$1") (pintype "bidirectional"))
    )
    (net (code "82") (name "Net-(R37-Pad2)") (class "Default")
      (node (ref "R37") (pin "2") (pinfunction "2_2") (pintype "passive"))
      (node (ref "SW7") (pin "P$1") (pinfunction "P$1_P$1") (pintype "bidirectional"))
    )
    (net (code "83") (name "Net-(R38-Pad2)") (class "Default")
      (node (ref "R38") (pin "2") (pinfunction "2_2") (pintype "passive"))
      (node (ref "SW8") (pin "P$1") (pinfunction "P$1_P$1") (pintype "bidirectional"))
    )
    (net (code "84") (name "Net-(R39-Pad2)") (class "Default")
      (node (ref "R39") (pin "2") (pinfunction "2_2") (pintype "passive"))
      (node (ref "SW9") (pin "P$1") (pinfunction "P$1_P$1") (pintype "bidirectional"))
    )
    (net (code "85") (name "Net-(R40-Pad2)") (class "Default")
      (node (ref "R40") (pin "2") (pinfunction "2_2") (pintype "passive"))
      (node (ref "SW10") (pin "P$1") (pinfunction "P$1_P$1") (pintype "bidirectional"))
    )
    (net (code "86") (name "Net-(U1-AD0{slash}GIO7)") (class "Default")
      (node (ref "L11") (pin "2") (pinfunction "2_2") (pintype "passive"))
      (node (ref "U1") (pin "16") (pinfunction "AD0/GIO7_16") (pintype "bidirectional"))
    )
    (net (code "87") (name "Net-(U1-AD1{slash}GIO8)") (class "Default")
      (node (ref "L13") (pin "2") (pinfunction "2_2") (pintype "passive"))
      (node (ref "U1") (pin "17") (pinfunction "AD1/GIO8_17") (pintype "bidirectional"))
    )
    (net (code "88") (name "Net-(U1-AD2{slash}GIO9)") (class "Default")
      (node (ref "R7") (pin "1") (pinfunction "1_1") (pintype "passive"))
      (node (ref "U1") (pin "19") (pinfunction "AD2/GIO9_19") (pintype "bidirectional"))
    )
    (net (code "89") (name "Net-(U1-BCLK{slash}GIO5)") (class "Default")
      (node (ref "L6") (pin "2") (pinfunction "2_2") (pintype "passive"))
      (node (ref "U1") (pin "14") (pinfunction "BCLK/GIO5_14") (pintype "bidirectional"))
    )
    (net (code "90") (name "Net-(U1-DCPL)") (class "Default")
      (node (ref "C23") (pin "1") (pinfunction "1_1") (pintype "passive"))
      (node (ref "U1") (pin "39") (pinfunction "DCPL_39") (pintype "bidirectional"))
    )
    (net (code "91") (name "Net-(U1-GIO3)") (class "Default")
      (node (ref "R5") (pin "1") (pinfunction "1_1") (pintype "passive"))
      (node (ref "U1") (pin "9") (pinfunction "GIO3_9") (pintype "bidirectional"))
    )
    (net (code "92") (name "Net-(U1-MCLK{slash}GIO4)") (class "Default")
      (node (ref "L5") (pin "2") (pinfunction "2_2") (pintype "passive"))
      (node (ref "U1") (pin "13") (pinfunction "MCLK/GIO4_13") (pintype "bidirectional"))
    )
    (net (code "93") (name "Net-(U1-RBIAS)") (class "Default")
      (node (ref "R4") (pin "2") (pinfunction "2_2") (pintype "passive"))
      (node (ref "U1") (pin "30") (pinfunction "RBIAS_30") (pintype "bidirectional"))
    )
    (net (code "94") (name "Net-(U1-RSTN)") (class "Default")
      (node (ref "L4") (pin "1") (pinfunction "1_1") (pintype "passive"))
      (node (ref "U1") (pin "11") (pinfunction "RSTN_11") (pintype "bidirectional"))
    )
    (net (code "95") (name "Net-(U1-USBN)") (class "Default")
      (node (ref "C14") (pin "1") (pinfunction "1_1") (pintype "passive"))
      (node (ref "R1") (pin "1") (pinfunction "1_1") (pintype "passive"))
      (node (ref "U1") (pin "1") (pinfunction "USBN_1") (pintype "bidirectional"))
    )
    (net (code "96") (name "Net-(U1-USBP)") (class "Default")
      (node (ref "C13") (pin "1") (pinfunction "1_1") (pintype "passive"))
      (node (ref "R2") (pin "1") (pinfunction "1_1") (pintype "passive"))
      (node (ref "U1") (pin "2") (pinfunction "USBP_2") (pintype "bidirectional"))
    )
    (net (code "97") (name "Net-(U1-WCLK{slash}GIO6)") (class "Default")
      (node (ref "L9") (pin "2") (pinfunction "2_2") (pintype "passive"))
      (node (ref "U1") (pin "15") (pinfunction "WCLK/GIO6_15") (pintype "bidirectional"))
    )
    (net (code "98") (name "Net-(U1-X0)") (class "Default")
      (node (ref "C24") (pin "1") (pinfunction "1_1") (pintype "passive"))
      (node (ref "U1") (pin "22") (pinfunction "X0_22") (pintype "bidirectional"))
      (node (ref "X1") (pin "3") (pinfunction "2_3") (pintype "passive"))
    )
    (net (code "99") (name "Net-(U1-X1)") (class "Default")
      (node (ref "C29") (pin "1") (pinfunction "1_1") (pintype "passive"))
      (node (ref "U1") (pin "21") (pinfunction "X1_21") (pintype "bidirectional"))
      (node (ref "X1") (pin "1") (pinfunction "1_1") (pintype "passive"))
    )
    (net (code "100") (name "Net-(U1-XPAEN)") (class "Default")
      (node (ref "L12") (pin "1") (pinfunction "1_1") (pintype "passive"))
      (node (ref "U1") (pin "36") (pinfunction "XPAEN_36") (pintype "bidirectional"))
    )
    (net (code "101") (name "Net-(U2-ANT)") (class "Default")
      (node (ref "L7") (pin "1") (pinfunction "1_1") (pintype "passive"))
      (node (ref "U2") (pin "11") (pinfunction "ANT_11") (pintype "bidirectional"))
    )
    (net (code "102") (name "Net-(U2-BIAS)") (class "Default")
      (node (ref "R8") (pin "2") (pinfunction "2_2") (pintype "passive"))
      (node (ref "U2") (pin "15") (pinfunction "BIAS_15") (pintype "bidirectional"))
    )
    (net (code "103") (name "Net-(U2-HGM)") (class "Default")
      (node (ref "R9") (pin "1") (pinfunction "1_1") (pintype "passive"))
      (node (ref "U2") (pin "7") (pinfunction "HGM_7") (pintype "bidirectional"))
    )
    (net (code "104") (name "Net-(U3-AVDD)") (class "Default")
      (node (ref "C48") (pin "1") (pinfunction "1_1") (pintype "passive"))
      (node (ref "U3") (pin "24") (pinfunction "AVDD_24") (pintype "bidirectional"))
    )
    (net (code "105") (name "Net-(U3-DVDD)") (class "Default")
      (node (ref "C49") (pin "1") (pinfunction "1_1") (pintype "passive"))
      (node (ref "U3") (pin "29") (pinfunction "DVDD_29") (pintype "bidirectional"))
    )
    (net (code "106") (name "Net-(U3-IN1_L)") (class "Default")
      (node (ref "C38") (pin "2") (pinfunction "2_2") (pintype "passive"))
      (node (ref "U3") (pin "13") (pinfunction "IN1_L_13") (pintype "bidirectional"))
    )
    (net (code "107") (name "Net-(U3-IN1_R)") (class "Default")
      (node (ref "C37") (pin "2") (pinfunction "2_2") (pintype "passive"))
      (node (ref "U3") (pin "14") (pinfunction "IN1_R_14") (pintype "bidirectional"))
    )
    (net (code "108") (name "Net-(U3-REF)") (class "Default")
      (node (ref "C50") (pin "1") (pinfunction "1_1") (pintype "passive"))
      (node (ref "U3") (pin "18") (pinfunction "REF_18") (pintype "bidirectional"))
    )
    (net (code "109") (name "Net-(U5-VIN)") (class "Default")
      (node (ref "F1") (pin "2") (pinfunction "2_2") (pintype "passive"))
      (node (ref "U5") (pin "1") (pinfunction "VIN_1") (pintype "bidirectional"))
    )
    (net (code "110") (name "Net-(U6-CLRPROG)") (class "Default")
      (node (ref "R19") (pin "2") (pinfunction "2_2") (pintype "passive"))
      (node (ref "R20") (pin "2") (pinfunction "2_2") (pintype "passive"))
      (node (ref "U6") (pin "2") (pinfunction "CLRPROG_2") (pintype "bidirectional"))
    )
    (net (code "111") (name "Net-(U6-C{slash}X)") (class "Default")
      (node (ref "R21") (pin "2") (pinfunction "2_2") (pintype "passive"))
      (node (ref "U6") (pin "5") (pinfunction "C/X_5") (pintype "bidirectional"))
      (node (ref "U6") (pin "6") (pinfunction "PROG_6") (pintype "bidirectional"))
    )
    (net (code "112") (name "Net-(U6-SW)") (class "Default")
      (node (ref "L17") (pin "1") (pinfunction "1_1") (pintype "passive"))
      (node (ref "U6") (pin "12") (pinfunction "SW_12") (pintype "bidirectional"))
    )
    (net (code "113") (name "Net-(U6-~{CHRG})") (class "Default")
      (node (ref "CHARGE") (pin "C") (pinfunction "C_C") (pintype "passive"))
      (node (ref "U6") (pin "7") (pinfunction "~{CHRG}_7") (pintype "bidirectional"))
    )
    (net (code "114") (name "Net-(U7F-DFSDM)") (class "Default")
      (node (ref "R41") (pin "1") (pinfunction "1_1") (pintype "passive"))
      (node (ref "U7") (pin "43") (pinfunction "DFSDM_43") (pintype "bidirectional"))
    )
    (net (code "115") (name "Net-(U7F-DFSDP)") (class "Default")
      (node (ref "R42") (pin "1") (pinfunction "1_1") (pintype "passive"))
      (node (ref "U7") (pin "42") (pinfunction "DFSDP_42") (pintype "bidirectional"))
    )
    (net (code "116") (name "Net-(U7F-FWUP)") (class "Default")
      (node (ref "R43") (pin "2") (pinfunction "2_2") (pintype "passive"))
      (node (ref "U7") (pin "53") (pinfunction "FWUP_53") (pintype "bidirectional"))
    )
    (net (code "117") (name "Net-(U7F-VBG)") (class "Default")
      (node (ref "C68") (pin "1") (pinfunction "1_1") (pintype "passive"))
      (node (ref "R32") (pin "2") (pinfunction "2_2") (pintype "passive"))
      (node (ref "U7") (pin "40") (pinfunction "VBG_40") (pintype "bidirectional"))
    )
    (net (code "118") (name "Net-(U7F-XIN)") (class "Default")
      (node (ref "C30") (pin "1") (pinfunction "1_1") (pintype "passive"))
      (node (ref "U7") (pin "36") (pinfunction "XIN_36") (pintype "bidirectional"))
      (node (ref "X3") (pin "X2") (pinfunction "2_X2") (pintype "passive"))
    )
    (net (code "119") (name "Net-(U7F-XOUT)") (class "Default")
      (node (ref "C56") (pin "1") (pinfunction "1_1") (pintype "passive"))
      (node (ref "U7") (pin "35") (pinfunction "XOUT_35") (pintype "bidirectional"))
      (node (ref "X3") (pin "X1") (pinfunction "1_X1") (pintype "passive"))
    )
    (net (code "120") (name "Net-(U8-SNS3)") (class "Default")
      (node (ref "C58") (pin "1") (pinfunction "1_1") (pintype "passive"))
      (node (ref "U8") (pin "8") (pinfunction "SNS3_8") (pintype "bidirectional"))
    )
    (net (code "121") (name "Net-(U8-SNS3K)") (class "Default")
      (node (ref "C58") (pin "2") (pinfunction "2_2") (pintype "passive"))
      (node (ref "R33") (pin "1") (pinfunction "1_1") (pintype "passive"))
      (node (ref "U8") (pin "9") (pinfunction "SNS3K_9") (pintype "bidirectional"))
    )
    (net (code "122") (name "Net-(U8-SNS4)") (class "Default")
      (node (ref "C59") (pin "1") (pinfunction "1_1") (pintype "passive"))
      (node (ref "U8") (pin "10") (pinfunction "SNS4_10") (pintype "bidirectional"))
    )
    (net (code "123") (name "Net-(U8-SNS4K)") (class "Default")
      (node (ref "C59") (pin "2") (pinfunction "2_2") (pintype "passive"))
      (node (ref "R34") (pin "1") (pinfunction "1_1") (pintype "passive"))
      (node (ref "U8") (pin "11") (pinfunction "SNS4K_11") (pintype "bidirectional"))
    )
    (net (code "124") (name "Net-(U8-SNS5)") (class "Default")
      (node (ref "C60") (pin "1") (pinfunction "1_1") (pintype "passive"))
      (node (ref "U8") (pin "12") (pinfunction "SNS5_12") (pintype "bidirectional"))
    )
    (net (code "125") (name "Net-(U8-SNS5K)") (class "Default")
      (node (ref "C60") (pin "2") (pinfunction "2_2") (pintype "passive"))
      (node (ref "R35") (pin "1") (pinfunction "1_1") (pintype "passive"))
      (node (ref "U8") (pin "13") (pinfunction "SNS5K_13") (pintype "bidirectional"))
    )
    (net (code "126") (name "Net-(U8-SNS6)") (class "Default")
      (node (ref "C61") (pin "1") (pinfunction "1_1") (pintype "passive"))
      (node (ref "U8") (pin "20") (pinfunction "SNS6_20") (pintype "bidirectional"))
    )
    (net (code "127") (name "Net-(U8-SNS6K)") (class "Default")
      (node (ref "C61") (pin "2") (pinfunction "2_2") (pintype "passive"))
      (node (ref "R37") (pin "1") (pinfunction "1_1") (pintype "passive"))
      (node (ref "U8") (pin "19") (pinfunction "SNS6K_19") (pintype "bidirectional"))
    )
    (net (code "128") (name "Net-(U8-SNS7K{slash}DETECT0)") (class "Default")
      (node (ref "C62") (pin "2") (pinfunction "2_2") (pintype "passive"))
      (node (ref "R38") (pin "1") (pinfunction "1_1") (pintype "passive"))
      (node (ref "U8") (pin "22") (pinfunction "SNS7K/DETECT0_22") (pintype "bidirectional"))
    )
    (net (code "129") (name "Net-(U8-SNS7{slash}DETECT1)") (class "Default")
      (node (ref "C62") (pin "1") (pinfunction "1_1") (pintype "passive"))
      (node (ref "U8") (pin "23") (pinfunction "SNS7/DETECT1_23") (pintype "bidirectional"))
    )
    (net (code "130") (name "Net-(U8-SNS8K{slash}DETECT3)") (class "Default")
      (node (ref "C66") (pin "2") (pinfunction "2_2") (pintype "passive"))
      (node (ref "R39") (pin "1") (pinfunction "1_1") (pintype "passive"))
      (node (ref "U8") (pin "25") (pinfunction "SNS8K/DETECT3_25") (pintype "bidirectional"))
    )
    (net (code "131") (name "Net-(U8-SNS8{slash}DETECT2)") (class "Default")
      (node (ref "C66") (pin "1") (pinfunction "1_1") (pintype "passive"))
      (node (ref "U8") (pin "24") (pinfunction "SNS8/DETECT2_24") (pintype "bidirectional"))
    )
    (net (code "132") (name "Net-(U8-SNS9K{slash}DETECT5)") (class "Default")
      (node (ref "C67") (pin "2") (pinfunction "2_2") (pintype "passive"))
      (node (ref "R40") (pin "1") (pinfunction "1_1") (pintype "passive"))
      (node (ref "U8") (pin "27") (pinfunction "SNS9K/DETECT5_27") (pintype "bidirectional"))
    )
    (net (code "133") (name "Net-(U8-SNS9{slash}DETECT4)") (class "Default")
      (node (ref "C67") (pin "1") (pinfunction "1_1") (pintype "passive"))
      (node (ref "U8") (pin "26") (pinfunction "SNS9/DETECT4_26") (pintype "bidirectional"))
    )
    (net (code "134") (name "Net-(U8-SNS10K{slash}SYNC)") (class "Default")
      (node (ref "C55") (pin "2") (pinfunction "2_2") (pintype "passive"))
      (node (ref "R26") (pin "1") (pinfunction "1_1") (pintype "passive"))
      (node (ref "U8") (pin "31") (pinfunction "SNS10K/SYNC_31") (pintype "bidirectional"))
    )
    (net (code "135") (name "Net-(U8-SNS10{slash}DETECT16)") (class "Default")
      (node (ref "C55") (pin "1") (pinfunction "1_1") (pintype "passive"))
      (node (ref "U8") (pin "30") (pinfunction "SNS10/DETECT16_30") (pintype "bidirectional"))
    )
    (net (code "136") (name "Net-(U8-~{RESET})") (class "Default")
      (node (ref "R36") (pin "1") (pinfunction "1_1") (pintype "passive"))
      (node (ref "U8") (pin "29") (pinfunction "~{RESET}_29") (pintype "bidirectional"))
    )
    (net (code "137") (name "Net-(U9-BYPASS)") (class "Default")
      (node (ref "C33") (pin "1") (pinfunction "1_1") (pintype "passive"))
      (node (ref "U9") (pin "1") (pinfunction "BYPASS_1") (pintype "bidirectional"))
    )
    (net (code "138") (name "Net-(U9-INA)") (class "Default")
      (node (ref "R12") (pin "2") (pinfunction "2_2") (pintype "passive"))
      (node (ref "R13") (pin "1") (pinfunction "1_1") (pintype "passive"))
      (node (ref "U9") (pin "8") (pinfunction "INA_8") (pintype "bidirectional"))
    )
    (net (code "139") (name "Net-(U9-INB)") (class "Default")
      (node (ref "R15") (pin "2") (pinfunction "2_2") (pintype "passive"))
      (node (ref "R16") (pin "1") (pinfunction "1_1") (pintype "passive"))
      (node (ref "U9") (pin "4") (pinfunction "INB_4") (pintype "bidirectional"))
    )
    (net (code "140") (name "Net-(U9-OUTB)") (class "Default")
      (node (ref "C39") (pin "1") (pinfunction "1_1") (pintype "passive"))
      (node (ref "R15") (pin "1") (pinfunction "1_1") (pintype "passive"))
      (node (ref "U9") (pin "5") (pinfunction "OUTB_5") (pintype "bidirectional"))
    )
    (net (code "141") (name "Net-(U9-SHUTDOWN)") (class "Default")
      (node (ref "R31") (pin "1") (pinfunction "1_1") (pintype "passive"))
      (node (ref "U9") (pin "3") (pinfunction "SHUTDOWN_3") (pintype "bidirectional"))
    )
    (net (code "142") (name "OUT_L") (class "Default")
      (node (ref "C36") (pin "2") (pinfunction "2_2") (pintype "passive"))
      (node (ref "PHONE_OUT") (pin "4") (pinfunction "L_4") (pintype "bidirectional"))
      (node (ref "R25") (pin "2") (pinfunction "2_2") (pintype "passive"))
    )
    (net (code "143") (name "OUT_R") (class "Default")
      (node (ref "C39") (pin "2") (pinfunction "2_2") (pintype "passive"))
      (node (ref "PHONE_OUT") (pin "1") (pinfunction "R_1") (pintype "bidirectional"))
    )
    (net (code "144") (name "PA_EN") (class "Default")
      (node (ref "L12") (pin "2") (pinfunction "2_2") (pintype "passive"))
      (node (ref "R10") (pin "2") (pinfunction "2_2") (pintype "passive"))
      (node (ref "U2") (pin "5") (pinfunction "PAEN_5") (pintype "bidirectional"))
    )
    (net (code "145") (name "PHONE_L") (class "Default")
      (node (ref "R28") (pin "1") (pinfunction "1_1") (pintype "passive"))
      (node (ref "U3") (pin "25") (pinfunction "HPL_25") (pintype "bidirectional"))
    )
    (net (code "146") (name "PHONE_R") (class "Default")
      (node (ref "R30") (pin "1") (pinfunction "1_1") (pintype "passive"))
      (node (ref "U3") (pin "27") (pinfunction "HPR_27") (pintype "bidirectional"))
    )
    (net (code "147") (name "PHONE_SENSE") (class "Default")
      (node (ref "PHONE_OUT") (pin "3") (pinfunction "L_SW_3") (pintype "bidirectional"))
      (node (ref "R24") (pin "1") (pinfunction "1_1") (pintype "passive"))
      (node (ref "U7") (pin "140") (pinfunction "PB14_140") (pintype "bidirectional"))
    )
    (net (code "148") (name "RED_BOT") (class "Default")
      (node (ref "TO_AUX2") (pin "4") (pinfunction "4_4") (pintype "bidirectional"))
      (node (ref "U7") (pin "139") (pinfunction "PC28_139") (pintype "bidirectional"))
    )
    (net (code "149") (name "RED_TOP") (class "Default")
      (node (ref "TO_AUX2") (pin "7") (pinfunction "7_7") (pintype "bidirectional"))
      (node (ref "U7") (pin "132") (pinfunction "PC21_132") (pintype "bidirectional"))
    )
    (net (code "150") (name "RESET_CC8531") (class "Default")
      (node (ref "CCD") (pin "7") (pinfunction "7_7") (pintype "bidirectional"))
      (node (ref "L4") (pin "2") (pinfunction "2_2") (pintype "passive"))
      (node (ref "U7") (pin "20") (pinfunction "PD7_20") (pintype "bidirectional"))
    )
    (net (code "151") (name "RESET_CODEC") (class "Default")
      (node (ref "U3") (pin "31") (pinfunction "~{RESET}_31") (pintype "bidirectional"))
      (node (ref "U7") (pin "16") (pinfunction "PD3_16") (pintype "bidirectional"))
    )
    (net (code "152") (name "RF_N") (class "Default")
      (node (ref "U1") (pin "25") (pinfunction "RF_N_25") (pintype "bidirectional"))
      (node (ref "U2") (pin "2") (pinfunction "RF_N_2") (pintype "bidirectional"))
    )
    (net (code "153") (name "RF_P") (class "Default")
      (node (ref "U1") (pin "24") (pinfunction "RF_P_24") (pintype "bidirectional"))
      (node (ref "U2") (pin "4") (pinfunction "RF_P_4") (pintype "bidirectional"))
    )
    (net (code "154") (name "SCLK") (class "Default")
      (node (ref "CCD") (pin "6") (pinfunction "6_6") (pintype "bidirectional"))
      (node (ref "MICROSD") (pin "CLK") (pinfunction "SCLK_CLK") (pintype "bidirectional"))
      (node (ref "TO_AUX1") (pin "1") (pinfunction "1_1") (pintype "bidirectional"))
      (node (ref "U1") (pin "4") (pinfunction "SCLK_4") (pintype "bidirectional"))
      (node (ref "U3") (pin "8") (pinfunction "SCLK/MFP3_8") (pintype "bidirectional"))
      (node (ref "U7") (pin "110") (pinfunction "PA27_110") (pintype "bidirectional"))
    )
    (net (code "155") (name "USBOTGID") (class "Default")
      (node (ref "U7") (pin "129") (pinfunction "PB11_129") (pintype "bidirectional"))
      (node (ref "USB2") (pin "4") (pinfunction "ID_4") (pintype "bidirectional"))
    )
    (net (code "156") (name "WCLK") (class "Default")
      (node (ref "L9") (pin "1") (pinfunction "1_1") (pintype "passive"))
      (node (ref "U3") (pin "3") (pinfunction "WCLK_3") (pintype "bidirectional"))
    )
    (net (code "157") (name "unconnected-(CCD-Pad3)") (class "Default")
      (node (ref "CCD") (pin "3") (pinfunction "3_3") (pintype "bidirectional"))
    )
    (net (code "158") (name "unconnected-(CCD-Pad4)") (class "Default")
      (node (ref "CCD") (pin "4") (pinfunction "4_4") (pintype "bidirectional"))
    )
    (net (code "159") (name "unconnected-(LINE_IN-R_SW-Pad2)") (class "Default")
      (node (ref "LINE_IN") (pin "2") (pinfunction "R_SW_2") (pintype "bidirectional"))
    )
    (net (code "160") (name "unconnected-(PHONE_OUT-R_SW-Pad2)") (class "Default")
      (node (ref "PHONE_OUT") (pin "2") (pinfunction "R_SW_2") (pintype "bidirectional"))
    )
    (net (code "161") (name "unconnected-(U1-SCL{slash}GIO10-Pad32)") (class "Default")
      (node (ref "U1") (pin "32") (pinfunction "SCL/GIO10_32") (pintype "bidirectional"))
    )
    (net (code "162") (name "unconnected-(U1-SDA{slash}GIO11-Pad33)") (class "Default")
      (node (ref "U1") (pin "33") (pinfunction "SDA/GIO11_33") (pintype "bidirectional"))
    )
    (net (code "163") (name "unconnected-(U2-RXTX-Pad3)") (class "Default")
      (node (ref "U2") (pin "3") (pinfunction "RXTX_3") (pintype "bidirectional"))
    )
    (net (code "164") (name "unconnected-(U3-GPIO{slash}MFP5-Pad32)") (class "Default")
      (node (ref "U3") (pin "32") (pinfunction "GPIO/MFP5_32") (pintype "bidirectional"))
    )
    (net (code "165") (name "unconnected-(U3-IN2_L-Pad15)") (class "Default")
      (node (ref "U3") (pin "15") (pinfunction "IN2_L_15") (pintype "bidirectional"))
    )
    (net (code "166") (name "unconnected-(U3-IN2_R-Pad16)") (class "Default")
      (node (ref "U3") (pin "16") (pinfunction "IN2_R_16") (pintype "bidirectional"))
    )
    (net (code "167") (name "unconnected-(U3-IN3_L-Pad20)") (class "Default")
      (node (ref "U3") (pin "20") (pinfunction "IN3_L_20") (pintype "bidirectional"))
    )
    (net (code "168") (name "unconnected-(U3-IN3_R-Pad21)") (class "Default")
      (node (ref "U3") (pin "21") (pinfunction "IN3_R_21") (pintype "bidirectional"))
    )
    (net (code "169") (name "unconnected-(U3-MICBIAS-Pad19)") (class "Default")
      (node (ref "U3") (pin "19") (pinfunction "MICBIAS_19") (pintype "bidirectional"))
    )
    (net (code "170") (name "unconnected-(U7A-PA0-Pad23)") (class "Default")
      (node (ref "U7") (pin "23") (pinfunction "PA0_23") (pintype "bidirectional"))
    )
    (net (code "171") (name "unconnected-(U7A-PA1-Pad24)") (class "Default")
      (node (ref "U7") (pin "24") (pinfunction "PA1_24") (pintype "bidirectional"))
    )
    (net (code "172") (name "unconnected-(U7A-PA3-Pad84)") (class "Default")
      (node (ref "U7") (pin "84") (pinfunction "PA3_84") (pintype "bidirectional"))
    )
    (net (code "173") (name "unconnected-(U7A-PA4-Pad83)") (class "Default")
      (node (ref "U7") (pin "83") (pinfunction "PA4_83") (pintype "bidirectional"))
    )
    (net (code "174") (name "unconnected-(U7A-PA5-Pad25)") (class "Default")
      (node (ref "U7") (pin "25") (pinfunction "PA5_25") (pintype "bidirectional"))
    )
    (net (code "175") (name "unconnected-(U7A-PA6-Pad82)") (class "Default")
      (node (ref "U7") (pin "82") (pinfunction "PA6_82") (pintype "bidirectional"))
    )
    (net (code "176") (name "unconnected-(U7A-PA8-Pad27)") (class "Default")
      (node (ref "U7") (pin "27") (pinfunction "PA8_27") (pintype "bidirectional"))
    )
    (net (code "177") (name "unconnected-(U7A-PA9-Pad2)") (class "Default")
      (node (ref "U7") (pin "2") (pinfunction "PA9_2") (pintype "bidirectional"))
    )
    (net (code "178") (name "unconnected-(U7A-PA10-Pad3)") (class "Default")
      (node (ref "U7") (pin "3") (pinfunction "PA10_3") (pintype "bidirectional"))
    )
    (net (code "179") (name "unconnected-(U7A-PA11-Pad4)") (class "Default")
      (node (ref "U7") (pin "4") (pinfunction "PA11_4") (pintype "bidirectional"))
    )
    (net (code "180") (name "unconnected-(U7A-PA12-Pad5)") (class "Default")
      (node (ref "U7") (pin "5") (pinfunction "PA12_5") (pintype "bidirectional"))
    )
    (net (code "181") (name "unconnected-(U7A-PA13-Pad6)") (class "Default")
      (node (ref "U7") (pin "6") (pinfunction "PA13_6") (pintype "bidirectional"))
    )
    (net (code "182") (name "unconnected-(U7A-PA14-Pad7)") (class "Default")
      (node (ref "U7") (pin "7") (pinfunction "PA14_7") (pintype "bidirectional"))
    )
    (net (code "183") (name "unconnected-(U7A-PA15-Pad8)") (class "Default")
      (node (ref "U7") (pin "8") (pinfunction "PA15_8") (pintype "bidirectional"))
    )
    (net (code "184") (name "unconnected-(U7A-PA16-Pad78)") (class "Default")
      (node (ref "U7") (pin "78") (pinfunction "PA16_78") (pintype "bidirectional"))
    )
    (net (code "185") (name "unconnected-(U7A-PA17-Pad9)") (class "Default")
      (node (ref "U7") (pin "9") (pinfunction "PA17_9") (pintype "bidirectional"))
    )
    (net (code "186") (name "unconnected-(U7A-PA18-Pad70)") (class "Default")
      (node (ref "U7") (pin "70") (pinfunction "PA18_70") (pintype "bidirectional"))
    )
    (net (code "187") (name "unconnected-(U7A-PA19-Pad71)") (class "Default")
      (node (ref "U7") (pin "71") (pinfunction "PA19_71") (pintype "bidirectional"))
    )
    (net (code "188") (name "unconnected-(U7A-PA21-Pad107)") (class "Default")
      (node (ref "U7") (pin "107") (pinfunction "PA21_107") (pintype "bidirectional"))
    )
    (net (code "189") (name "unconnected-(U7A-PA22-Pad81)") (class "Default")
      (node (ref "U7") (pin "81") (pinfunction "PA22_81") (pintype "bidirectional"))
    )
    (net (code "190") (name "unconnected-(U7A-PA23-Pad80)") (class "Default")
      (node (ref "U7") (pin "80") (pinfunction "PA23_80") (pintype "bidirectional"))
    )
    (net (code "191") (name "unconnected-(U7A-PA24-Pad79)") (class "Default")
      (node (ref "U7") (pin "79") (pinfunction "PA24_79") (pintype "bidirectional"))
    )
    (net (code "192") (name "unconnected-(U7A-PA28-Pad111)") (class "Default")
      (node (ref "U7") (pin "111") (pinfunction "PA28_111") (pintype "bidirectional"))
    )
    (net (code "193") (name "unconnected-(U7A-PA29-Pad112)") (class "Default")
      (node (ref "U7") (pin "112") (pinfunction "PA29_112") (pintype "bidirectional"))
    )
    (net (code "194") (name "unconnected-(U7B-PB0-Pad113)") (class "Default")
      (node (ref "U7") (pin "113") (pinfunction "PB0_113") (pintype "bidirectional"))
    )
    (net (code "195") (name "unconnected-(U7B-PB1-Pad114)") (class "Default")
      (node (ref "U7") (pin "114") (pinfunction "PB1_114") (pintype "bidirectional"))
    )
    (net (code "196") (name "unconnected-(U7B-PB2-Pad115)") (class "Default")
      (node (ref "U7") (pin "115") (pinfunction "PB2_115") (pintype "bidirectional"))
    )
    (net (code "197") (name "unconnected-(U7B-PB3-Pad118)") (class "Default")
      (node (ref "U7") (pin "118") (pinfunction "PB3_118") (pintype "bidirectional"))
    )
    (net (code "198") (name "unconnected-(U7B-PB4-Pad119)") (class "Default")
      (node (ref "U7") (pin "119") (pinfunction "PB4_119") (pintype "bidirectional"))
    )
    (net (code "199") (name "unconnected-(U7B-PB5-Pad120)") (class "Default")
      (node (ref "U7") (pin "120") (pinfunction "PB5_120") (pintype "bidirectional"))
    )
    (net (code "200") (name "unconnected-(U7B-PB6-Pad121)") (class "Default")
      (node (ref "U7") (pin "121") (pinfunction "PB6_121") (pintype "bidirectional"))
    )
    (net (code "201") (name "unconnected-(U7B-PB7-Pad122)") (class "Default")
      (node (ref "U7") (pin "122") (pinfunction "PB7_122") (pintype "bidirectional"))
    )
    (net (code "202") (name "unconnected-(U7B-PB8-Pad123)") (class "Default")
      (node (ref "U7") (pin "123") (pinfunction "PB8_123") (pintype "bidirectional"))
    )
    (net (code "203") (name "unconnected-(U7B-PB9-Pad127)") (class "Default")
      (node (ref "U7") (pin "127") (pinfunction "PB9_127") (pintype "bidirectional"))
    )
    (net (code "204") (name "unconnected-(U7B-PB10-Pad128)") (class "Default")
      (node (ref "U7") (pin "128") (pinfunction "PB10_128") (pintype "bidirectional"))
    )
    (net (code "205") (name "unconnected-(U7B-PB12-Pad86)") (class "Default")
      (node (ref "U7") (pin "86") (pinfunction "PB12_86") (pintype "bidirectional"))
    )
    (net (code "206") (name "unconnected-(U7B-PB13-Pad87)") (class "Default")
      (node (ref "U7") (pin "87") (pinfunction "PB13_87") (pintype "bidirectional"))
    )
    (net (code "207") (name "unconnected-(U7B-PB15-Pad76)") (class "Default")
      (node (ref "U7") (pin "76") (pinfunction "PB15_76") (pintype "bidirectional"))
    )
    (net (code "208") (name "unconnected-(U7B-PB16-Pad77)") (class "Default")
      (node (ref "U7") (pin "77") (pinfunction "PB16_77") (pintype "bidirectional"))
    )
    (net (code "209") (name "unconnected-(U7B-PB17-Pad88)") (class "Default")
      (node (ref "U7") (pin "88") (pinfunction "PB17_88") (pintype "bidirectional"))
    )
    (net (code "210") (name "unconnected-(U7B-PB18-Pad89)") (class "Default")
      (node (ref "U7") (pin "89") (pinfunction "PB18_89") (pintype "bidirectional"))
    )
    (net (code "211") (name "unconnected-(U7B-PB19-Pad90)") (class "Default")
      (node (ref "U7") (pin "90") (pinfunction "PB19_90") (pintype "bidirectional"))
    )
    (net (code "212") (name "unconnected-(U7B-PB20-Pad91)") (class "Default")
      (node (ref "U7") (pin "91") (pinfunction "PB20_91") (pintype "bidirectional"))
    )
    (net (code "213") (name "unconnected-(U7B-PB21-Pad92)") (class "Default")
      (node (ref "U7") (pin "92") (pinfunction "PB21_92") (pintype "bidirectional"))
    )
    (net (code "214") (name "unconnected-(U7B-PB22-Pad141)") (class "Default")
      (node (ref "U7") (pin "141") (pinfunction "PB22_141") (pintype "bidirectional"))
    )
    (net (code "215") (name "unconnected-(U7B-PB23-Pad142)") (class "Default")
      (node (ref "U7") (pin "142") (pinfunction "PB23_142") (pintype "bidirectional"))
    )
    (net (code "216") (name "unconnected-(U7B-PB24-Pad143)") (class "Default")
      (node (ref "U7") (pin "143") (pinfunction "PB24_143") (pintype "bidirectional"))
    )
    (net (code "217") (name "unconnected-(U7B-PB25-Pad144)") (class "Default")
      (node (ref "U7") (pin "144") (pinfunction "PB25_144") (pintype "bidirectional"))
    )
    (net (code "218") (name "unconnected-(U7B-PB26-Pad1)") (class "Default")
      (node (ref "U7") (pin "1") (pinfunction "PB26_1") (pintype "bidirectional"))
    )
    (net (code "219") (name "unconnected-(U7B-PB27-Pad68)") (class "Default")
      (node (ref "U7") (pin "68") (pinfunction "PB27_68") (pintype "bidirectional"))
    )
    (net (code "220") (name "unconnected-(U7B-PB28-Pad28)") (class "Default")
      (node (ref "U7") (pin "28") (pinfunction "PB28_28") (pintype "bidirectional"))
    )
    (net (code "221") (name "unconnected-(U7B-PB29-Pad29)") (class "Default")
      (node (ref "U7") (pin "29") (pinfunction "PB29_29") (pintype "bidirectional"))
    )
    (net (code "222") (name "unconnected-(U7B-PB30-Pad30)") (class "Default")
      (node (ref "U7") (pin "30") (pinfunction "PB30_30") (pintype "bidirectional"))
    )
    (net (code "223") (name "unconnected-(U7B-PB31-Pad31)") (class "Default")
      (node (ref "U7") (pin "31") (pinfunction "PB31_31") (pintype "bidirectional"))
    )
    (net (code "224") (name "unconnected-(U7C-PC1-Pad55)") (class "Default")
      (node (ref "U7") (pin "55") (pinfunction "PC1_55") (pintype "bidirectional"))
    )
    (net (code "225") (name "unconnected-(U7C-PC2-Pad59)") (class "Default")
      (node (ref "U7") (pin "59") (pinfunction "PC2_59") (pintype "bidirectional"))
    )
    (net (code "226") (name "unconnected-(U7C-PC3-Pad60)") (class "Default")
      (node (ref "U7") (pin "60") (pinfunction "PC3_60") (pintype "bidirectional"))
    )
    (net (code "227") (name "unconnected-(U7C-PC4-Pad116)") (class "Default")
      (node (ref "U7") (pin "116") (pinfunction "PC4_116") (pintype "bidirectional"))
    )
    (net (code "228") (name "unconnected-(U7C-PC5-Pad63)") (class "Default")
      (node (ref "U7") (pin "63") (pinfunction "PC5_63") (pintype "bidirectional"))
    )
    (net (code "229") (name "unconnected-(U7C-PC6-Pad64)") (class "Default")
      (node (ref "U7") (pin "64") (pinfunction "PC6_64") (pintype "bidirectional"))
    )
    (net (code "230") (name "unconnected-(U7C-PC7-Pad65)") (class "Default")
      (node (ref "U7") (pin "65") (pinfunction "PC7_65") (pintype "bidirectional"))
    )
    (net (code "231") (name "unconnected-(U7C-PC10-Pad117)") (class "Default")
      (node (ref "U7") (pin "117") (pinfunction "PC10_117") (pintype "bidirectional"))
    )
    (net (code "232") (name "unconnected-(U7C-PC11-Pad93)") (class "Default")
      (node (ref "U7") (pin "93") (pinfunction "PC11_93") (pintype "bidirectional"))
    )
    (net (code "233") (name "unconnected-(U7C-PC12-Pad94)") (class "Default")
      (node (ref "U7") (pin "94") (pinfunction "PC12_94") (pintype "bidirectional"))
    )
    (net (code "234") (name "unconnected-(U7C-PC13-Pad95)") (class "Default")
      (node (ref "U7") (pin "95") (pinfunction "PC13_95") (pintype "bidirectional"))
    )
    (net (code "235") (name "unconnected-(U7C-PC14-Pad96)") (class "Default")
      (node (ref "U7") (pin "96") (pinfunction "PC14_96") (pintype "bidirectional"))
    )
    (net (code "236") (name "unconnected-(U7C-PC15-Pad97)") (class "Default")
      (node (ref "U7") (pin "97") (pinfunction "PC15_97") (pintype "bidirectional"))
    )
    (net (code "237") (name "unconnected-(U7C-PC16-Pad98)") (class "Default")
      (node (ref "U7") (pin "98") (pinfunction "PC16_98") (pintype "bidirectional"))
    )
    (net (code "238") (name "unconnected-(U7C-PC17-Pad99)") (class "Default")
      (node (ref "U7") (pin "99") (pinfunction "PC17_99") (pintype "bidirectional"))
    )
    (net (code "239") (name "unconnected-(U7C-PC18-Pad100)") (class "Default")
      (node (ref "U7") (pin "100") (pinfunction "PC18_100") (pintype "bidirectional"))
    )
    (net (code "240") (name "unconnected-(U7C-PC20-Pad131)") (class "Default")
      (node (ref "U7") (pin "131") (pinfunction "PC20_131") (pintype "bidirectional"))
    )
    (net (code "241") (name "unconnected-(U7C-PC26-Pad137)") (class "Default")
      (node (ref "U7") (pin "137") (pinfunction "PC26_137") (pintype "bidirectional"))
    )
    (net (code "242") (name "unconnected-(U7C-PC27-Pad138)") (class "Default")
      (node (ref "U7") (pin "138") (pinfunction "PC27_138") (pintype "bidirectional"))
    )
    (net (code "243") (name "unconnected-(U7C-PC29-Pad102)") (class "Default")
      (node (ref "U7") (pin "102") (pinfunction "PC29_102") (pintype "bidirectional"))
    )
    (net (code "244") (name "unconnected-(U7C-PC30-Pad103)") (class "Default")
      (node (ref "U7") (pin "103") (pinfunction "PC30_103") (pintype "bidirectional"))
    )
    (net (code "245") (name "unconnected-(U7D-PD0-Pad13)") (class "Default")
      (node (ref "U7") (pin "13") (pinfunction "PD0_13") (pintype "bidirectional"))
    )
    (net (code "246") (name "unconnected-(U7D-PD1-Pad14)") (class "Default")
      (node (ref "U7") (pin "14") (pinfunction "PD1_14") (pintype "bidirectional"))
    )
    (net (code "247") (name "unconnected-(U7D-PD4-Pad17)") (class "Default")
      (node (ref "U7") (pin "17") (pinfunction "PD4_17") (pintype "bidirectional"))
    )
    (net (code "248") (name "unconnected-(U7D-PD5-Pad18)") (class "Default")
      (node (ref "U7") (pin "18") (pinfunction "PD5_18") (pintype "bidirectional"))
    )
    (net (code "249") (name "unconnected-(U7D-PD6-Pad19)") (class "Default")
      (node (ref "U7") (pin "19") (pinfunction "PD6_19") (pintype "bidirectional"))
    )
    (net (code "250") (name "unconnected-(U7F-NRST-Pad69)") (class "Default")
      (node (ref "U7") (pin "69") (pinfunction "NRST_69") (pintype "bidirectional"))
    )
    (net (code "251") (name "unconnected-(U7F-SHDN-Pad50)") (class "Default")
      (node (ref "U7") (pin "50") (pinfunction "SHDN_50") (pintype "bidirectional"))
    )
    (net (code "252") (name "unconnected-(U7F-TST-Pad51)") (class "Default")
      (node (ref "U7") (pin "51") (pinfunction "TST_51") (pintype "bidirectional"))
    )
    (net (code "253") (name "unconnected-(U7F-XIN32-Pad48)") (class "Default")
      (node (ref "U7") (pin "48") (pinfunction "XIN32_48") (pintype "bidirectional"))
    )
    (net (code "254") (name "unconnected-(U7F-XOUT32-Pad49)") (class "Default")
      (node (ref "U7") (pin "49") (pinfunction "XOUT32_49") (pintype "bidirectional"))
    )
    (net (code "255") (name "unconnected-(U8-SNS0-Pad32)") (class "Default")
      (node (ref "U8") (pin "32") (pinfunction "SNS0_32") (pintype "bidirectional"))
    )
    (net (code "256") (name "unconnected-(U8-SNS0K-Pad1)") (class "Default")
      (node (ref "U8") (pin "1") (pinfunction "SNS0K_1") (pintype "bidirectional"))
    )
    (net (code "257") (name "unconnected-(U8-SNS1-Pad2)") (class "Default")
      (node (ref "U8") (pin "2") (pinfunction "SNS1_2") (pintype "bidirectional"))
    )
    (net (code "258") (name "unconnected-(U8-SNS1K-Pad3)") (class "Default")
      (node (ref "U8") (pin "3") (pinfunction "SNS1K_3") (pintype "bidirectional"))
    )
    (net (code "259") (name "unconnected-(U8-SNS2-Pad7)") (class "Default")
      (node (ref "U8") (pin "7") (pinfunction "SNS2_7") (pintype "bidirectional"))
    )
    (net (code "260") (name "unconnected-(U8-SNS2K-Pad6)") (class "Default")
      (node (ref "U8") (pin "6") (pinfunction "SNS2K_6") (pintype "bidirectional"))
    )
    (net (code "261") (name "unconnected-(USB1-ID-Pad4)") (class "Default")
      (node (ref "USB1") (pin "4") (pinfunction "ID_4") (pintype "bidirectional"))
    )
  )
)
